# 01SignalDetect.net
KiCad netlist of a schematic drawn in Altium Designer
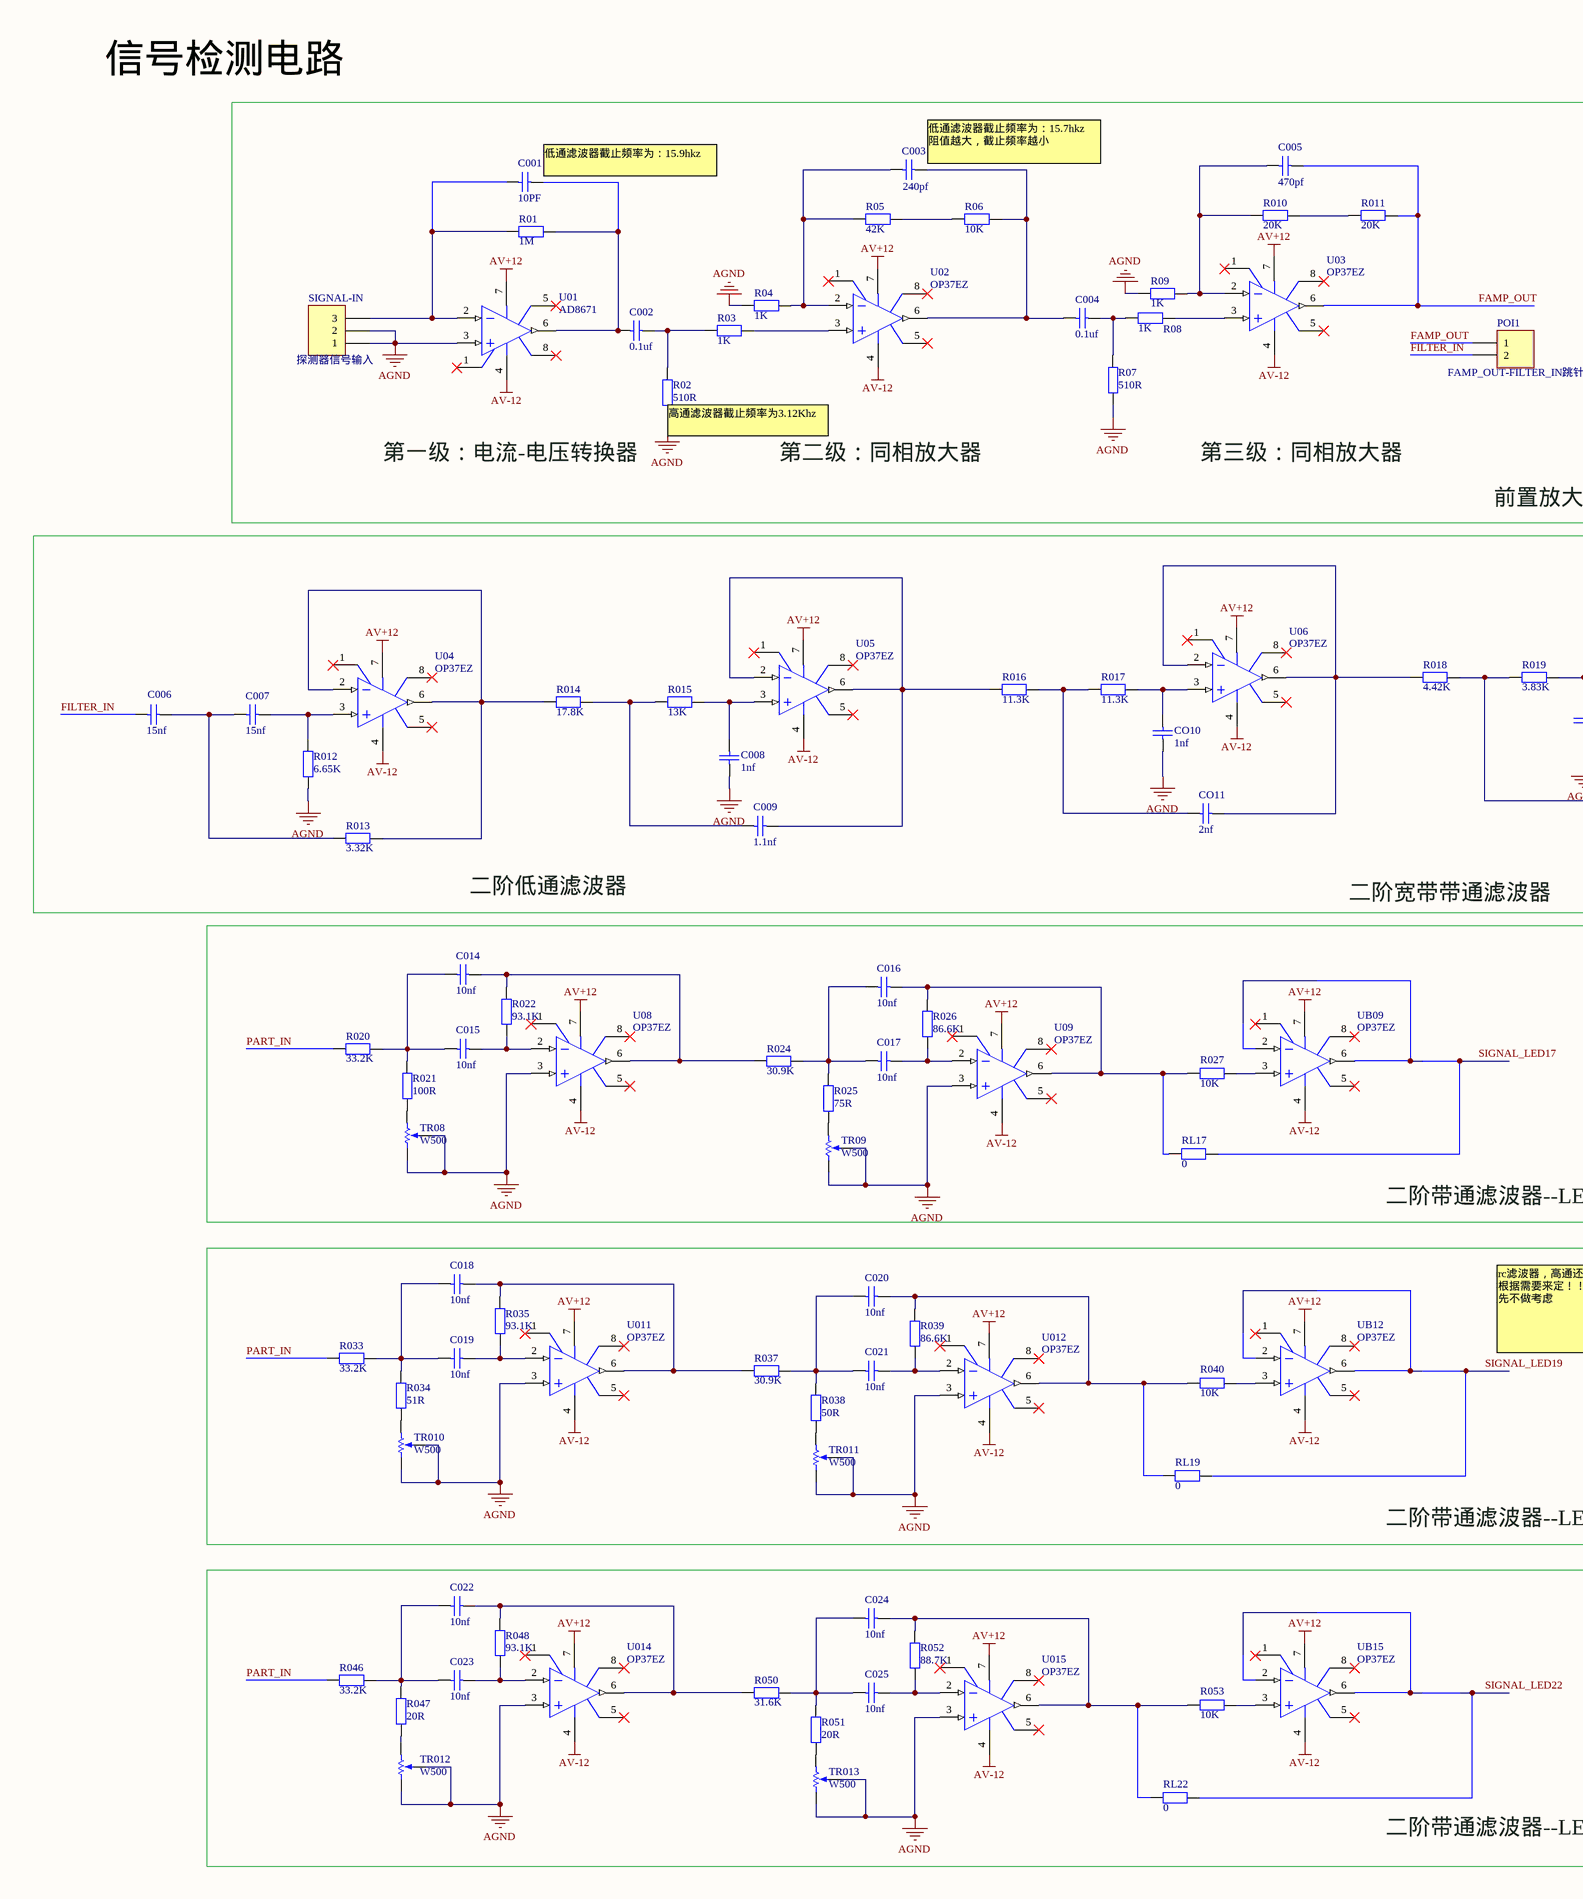
[diagram p0: 01SignalDetect.SchDoc, left]
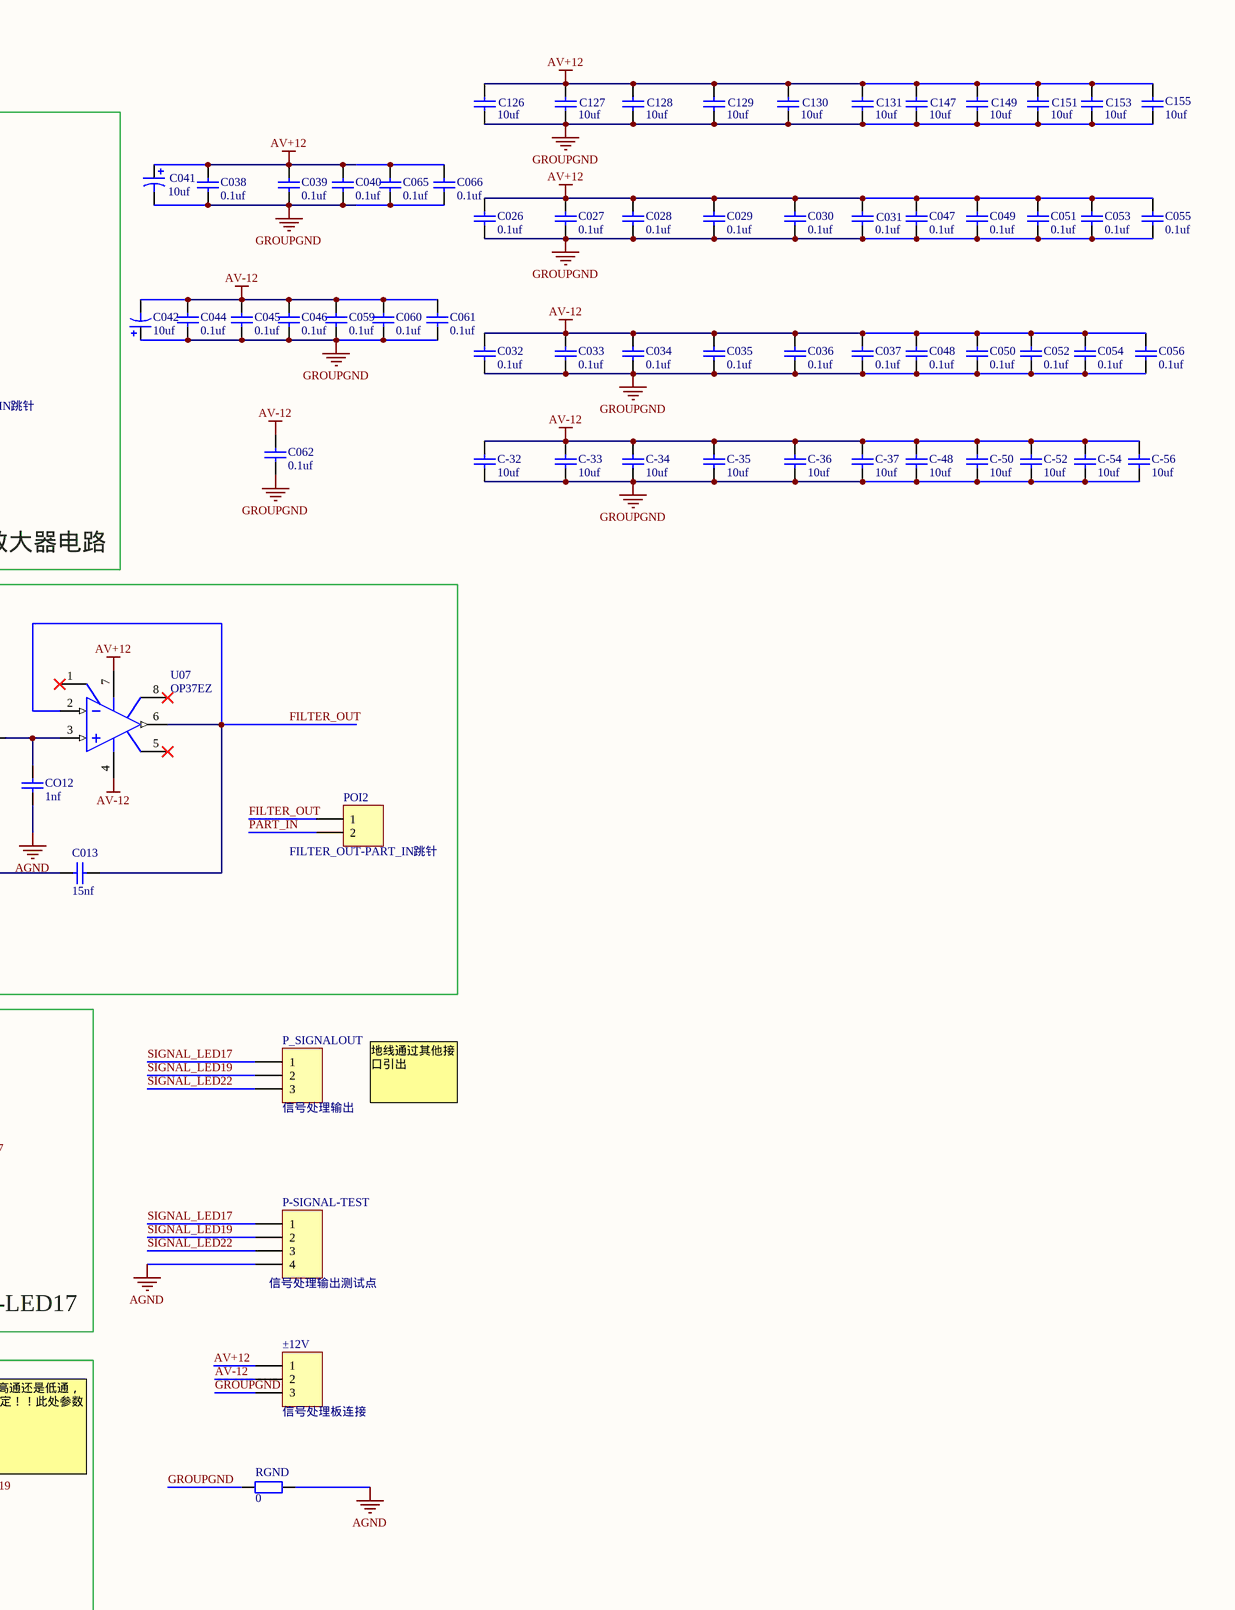
[diagram p1: 01SignalDetect.SchDoc, right]

(export (version "E")
  (design (tool "Eeschema 10.0.6"))
  (components
    (comp (ref "C-32")
      (value "10uf")
      (footprint "CC0805")
      (description "Capacitor")
      (fields (field (name "Comment") "Cap") (field (name "PUBLISHER") "Altium Limited"))
      (libsource (lib "Miscellaneous Devices") (part "Cap"))
    )
    (comp (ref "C-33")
      (value "10uf")
      (footprint "CC0805")
      (description "Capacitor")
      (fields (field (name "Comment") "Cap") (field (name "PUBLISHER") "Altium Limited"))
      (libsource (lib "Miscellaneous Devices") (part "Cap"))
    )
    (comp (ref "C-34")
      (value "10uf")
      (footprint "CC0805")
      (description "Capacitor")
      (fields (field (name "Comment") "Cap") (field (name "PUBLISHER") "Altium Limited"))
      (libsource (lib "Miscellaneous Devices") (part "Cap"))
    )
    (comp (ref "C-35")
      (value "10uf")
      (footprint "CC0805")
      (description "Capacitor")
      (fields (field (name "Comment") "Cap") (field (name "PUBLISHER") "Altium Limited"))
      (libsource (lib "Miscellaneous Devices") (part "Cap"))
    )
    (comp (ref "C-36")
      (value "10uf")
      (footprint "CC0805")
      (description "Capacitor")
      (fields (field (name "Comment") "Cap") (field (name "PUBLISHER") "Altium Limited"))
      (libsource (lib "Miscellaneous Devices") (part "Cap"))
    )
    (comp (ref "C-37")
      (value "10uf")
      (footprint "CC0805")
      (description "Capacitor")
      (fields (field (name "Comment") "Cap") (field (name "PUBLISHER") "Altium Limited"))
      (libsource (lib "Miscellaneous Devices") (part "Cap"))
    )
    (comp (ref "C-48")
      (value "10uf")
      (footprint "CC0805")
      (description "Capacitor")
      (fields (field (name "Comment") "Cap") (field (name "PUBLISHER") "Altium Limited"))
      (libsource (lib "Miscellaneous Devices") (part "Cap"))
    )
    (comp (ref "C-50")
      (value "10uf")
      (footprint "CC0805")
      (description "Capacitor")
      (fields (field (name "Comment") "Cap") (field (name "PUBLISHER") "Altium Limited"))
      (libsource (lib "Miscellaneous Devices") (part "Cap"))
    )
    (comp (ref "C-52")
      (value "10uf")
      (footprint "CC0805")
      (description "Capacitor")
      (fields (field (name "Comment") "Cap") (field (name "PUBLISHER") "Altium Limited"))
      (libsource (lib "Miscellaneous Devices") (part "Cap"))
    )
    (comp (ref "C-54")
      (value "10uf")
      (footprint "CC0805")
      (description "Capacitor")
      (fields (field (name "Comment") "Cap") (field (name "PUBLISHER") "Altium Limited"))
      (libsource (lib "Miscellaneous Devices") (part "Cap"))
    )
    (comp (ref "C-56")
      (value "10uf")
      (footprint "CC0805")
      (description "Capacitor")
      (fields (field (name "Comment") "Cap") (field (name "PUBLISHER") "Altium Limited"))
      (libsource (lib "Miscellaneous Devices") (part "Cap"))
    )
    (comp (ref "C001")
      (value "10PF")
      (footprint "CC0805")
      (description "Capacitor")
      (fields (field (name "Comment") "Cap") (field (name "PUBLISHER") "Altium Limited"))
      (libsource (lib "Miscellaneous Devices") (part "Cap"))
    )
    (comp (ref "C002")
      (value "0.1uf")
      (footprint "CC0805")
      (description "Capacitor")
      (fields (field (name "Comment") "Cap") (field (name "PUBLISHER") "Altium Limited"))
      (libsource (lib "Miscellaneous Devices") (part "Cap"))
    )
    (comp (ref "C003")
      (value "240pf")
      (footprint "CC0805")
      (description "Capacitor")
      (fields (field (name "Comment") "Cap") (field (name "PUBLISHER") "Altium Limited"))
      (libsource (lib "Miscellaneous Devices") (part "Cap"))
    )
    (comp (ref "C004")
      (value "0.1uf")
      (footprint "CC0805")
      (description "Capacitor")
      (fields (field (name "Comment") "Cap") (field (name "PUBLISHER") "Altium Limited"))
      (libsource (lib "Miscellaneous Devices") (part "Cap"))
    )
    (comp (ref "C005")
      (value "470pf")
      (footprint "CC0805")
      (description "Capacitor")
      (fields (field (name "Comment") "Cap") (field (name "PUBLISHER") "Altium Limited"))
      (libsource (lib "Miscellaneous Devices") (part "Cap"))
    )
    (comp (ref "C006")
      (value "15nf")
      (footprint "CC0805")
      (description "Capacitor")
      (fields (field (name "Comment") "Cap") (field (name "PUBLISHER") "Altium Limited"))
      (libsource (lib "Miscellaneous Devices") (part "Cap"))
    )
    (comp (ref "C007")
      (value "15nf")
      (footprint "CC0805")
      (description "Capacitor")
      (fields (field (name "Comment") "Cap") (field (name "PUBLISHER") "Altium Limited"))
      (libsource (lib "Miscellaneous Devices") (part "Cap"))
    )
    (comp (ref "C008")
      (value "1nf")
      (footprint "CC0805")
      (description "Capacitor")
      (fields (field (name "Comment") "Cap") (field (name "PUBLISHER") "Altium Limited"))
      (libsource (lib "Miscellaneous Devices") (part "Cap"))
    )
    (comp (ref "C009")
      (value "1.1nf")
      (footprint "CC0805")
      (description "Capacitor")
      (fields (field (name "Comment") "Cap") (field (name "PUBLISHER") "Altium Limited"))
      (libsource (lib "Miscellaneous Devices") (part "Cap"))
    )
    (comp (ref "C013")
      (value "15nf")
      (footprint "CC0805")
      (description "Capacitor")
      (fields (field (name "Comment") "Cap") (field (name "PUBLISHER") "Altium Limited"))
      (libsource (lib "Miscellaneous Devices") (part "Cap"))
    )
    (comp (ref "C014")
      (value "10nf")
      (footprint "校正电容")
      (description "Capacitor")
      (fields (field (name "Comment") "Cap") (field (name "PUBLISHER") "Altium Limited"))
      (libsource (lib "Miscellaneous Devices") (part "Cap"))
    )
    (comp (ref "C015")
      (value "10nf")
      (footprint "校正电容")
      (description "Capacitor")
      (fields (field (name "Comment") "Cap") (field (name "PUBLISHER") "Altium Limited"))
      (libsource (lib "Miscellaneous Devices") (part "Cap"))
    )
    (comp (ref "C016")
      (value "10nf")
      (footprint "校正电容")
      (description "Capacitor")
      (fields (field (name "Comment") "Cap") (field (name "PUBLISHER") "Altium Limited"))
      (libsource (lib "Miscellaneous Devices") (part "Cap"))
    )
    (comp (ref "C017")
      (value "10nf")
      (footprint "校正电容")
      (description "Capacitor")
      (fields (field (name "Comment") "Cap") (field (name "PUBLISHER") "Altium Limited"))
      (libsource (lib "Miscellaneous Devices") (part "Cap"))
    )
    (comp (ref "C018")
      (value "10nf")
      (footprint "校正电容")
      (description "Capacitor")
      (fields (field (name "Comment") "Cap") (field (name "PUBLISHER") "Altium Limited"))
      (libsource (lib "Miscellaneous Devices") (part "Cap"))
    )
    (comp (ref "C019")
      (value "10nf")
      (footprint "校正电容")
      (description "Capacitor")
      (fields (field (name "Comment") "Cap") (field (name "PUBLISHER") "Altium Limited"))
      (libsource (lib "Miscellaneous Devices") (part "Cap"))
    )
    (comp (ref "C020")
      (value "10nf")
      (footprint "校正电容")
      (description "Capacitor")
      (fields (field (name "Comment") "Cap") (field (name "PUBLISHER") "Altium Limited"))
      (libsource (lib "Miscellaneous Devices") (part "Cap"))
    )
    (comp (ref "C021")
      (value "10nf")
      (footprint "校正电容")
      (description "Capacitor")
      (fields (field (name "Comment") "Cap") (field (name "PUBLISHER") "Altium Limited"))
      (libsource (lib "Miscellaneous Devices") (part "Cap"))
    )
    (comp (ref "C022")
      (value "10nf")
      (footprint "校正电容")
      (description "Capacitor")
      (fields (field (name "Comment") "Cap") (field (name "PUBLISHER") "Altium Limited"))
      (libsource (lib "Miscellaneous Devices") (part "Cap"))
    )
    (comp (ref "C023")
      (value "10nf")
      (footprint "校正电容")
      (description "Capacitor")
      (fields (field (name "Comment") "Cap") (field (name "PUBLISHER") "Altium Limited"))
      (libsource (lib "Miscellaneous Devices") (part "Cap"))
    )
    (comp (ref "C024")
      (value "10nf")
      (footprint "校正电容")
      (description "Capacitor")
      (fields (field (name "Comment") "Cap") (field (name "PUBLISHER") "Altium Limited"))
      (libsource (lib "Miscellaneous Devices") (part "Cap"))
    )
    (comp (ref "C025")
      (value "10nf")
      (footprint "校正电容")
      (description "Capacitor")
      (fields (field (name "Comment") "Cap") (field (name "PUBLISHER") "Altium Limited"))
      (libsource (lib "Miscellaneous Devices") (part "Cap"))
    )
    (comp (ref "C026")
      (value "0.1uf")
      (footprint "CC0805")
      (description "Capacitor")
      (fields (field (name "Comment") "Cap") (field (name "PUBLISHER") "Altium Limited"))
      (libsource (lib "Miscellaneous Devices") (part "Cap"))
    )
    (comp (ref "C027")
      (value "0.1uf")
      (footprint "CC0805")
      (description "Capacitor")
      (fields (field (name "Comment") "Cap") (field (name "PUBLISHER") "Altium Limited"))
      (libsource (lib "Miscellaneous Devices") (part "Cap"))
    )
    (comp (ref "C028")
      (value "0.1uf")
      (footprint "CC0805")
      (description "Capacitor")
      (fields (field (name "Comment") "Cap") (field (name "PUBLISHER") "Altium Limited"))
      (libsource (lib "Miscellaneous Devices") (part "Cap"))
    )
    (comp (ref "C029")
      (value "0.1uf")
      (footprint "CC0805")
      (description "Capacitor")
      (fields (field (name "Comment") "Cap") (field (name "PUBLISHER") "Altium Limited"))
      (libsource (lib "Miscellaneous Devices") (part "Cap"))
    )
    (comp (ref "C030")
      (value "0.1uf")
      (footprint "CC0805")
      (description "Capacitor")
      (fields (field (name "Comment") "Cap") (field (name "PUBLISHER") "Altium Limited"))
      (libsource (lib "Miscellaneous Devices") (part "Cap"))
    )
    (comp (ref "C031")
      (value "0.1uf")
      (footprint "CC0805")
      (description "Capacitor")
      (fields (field (name "Comment") "Cap") (field (name "PUBLISHER") "Altium Limited"))
      (libsource (lib "Miscellaneous Devices") (part "Cap"))
    )
    (comp (ref "C032")
      (value "0.1uf")
      (footprint "CC0805")
      (description "Capacitor")
      (fields (field (name "Comment") "Cap") (field (name "PUBLISHER") "Altium Limited"))
      (libsource (lib "Miscellaneous Devices") (part "Cap"))
    )
    (comp (ref "C033")
      (value "0.1uf")
      (footprint "CC0805")
      (description "Capacitor")
      (fields (field (name "Comment") "Cap") (field (name "PUBLISHER") "Altium Limited"))
      (libsource (lib "Miscellaneous Devices") (part "Cap"))
    )
    (comp (ref "C034")
      (value "0.1uf")
      (footprint "CC0805")
      (description "Capacitor")
      (fields (field (name "Comment") "Cap") (field (name "PUBLISHER") "Altium Limited"))
      (libsource (lib "Miscellaneous Devices") (part "Cap"))
    )
    (comp (ref "C035")
      (value "0.1uf")
      (footprint "CC0805")
      (description "Capacitor")
      (fields (field (name "Comment") "Cap") (field (name "PUBLISHER") "Altium Limited"))
      (libsource (lib "Miscellaneous Devices") (part "Cap"))
    )
    (comp (ref "C036")
      (value "0.1uf")
      (footprint "CC0805")
      (description "Capacitor")
      (fields (field (name "Comment") "Cap") (field (name "PUBLISHER") "Altium Limited"))
      (libsource (lib "Miscellaneous Devices") (part "Cap"))
    )
    (comp (ref "C037")
      (value "0.1uf")
      (footprint "CC0805")
      (description "Capacitor")
      (fields (field (name "Comment") "Cap") (field (name "PUBLISHER") "Altium Limited"))
      (libsource (lib "Miscellaneous Devices") (part "Cap"))
    )
    (comp (ref "C038")
      (value "0.1uf")
      (footprint "CC0805")
      (description "Capacitor")
      (fields (field (name "Comment") "Cap") (field (name "PUBLISHER") "Altium Limited"))
      (libsource (lib "Miscellaneous Devices") (part "Cap"))
    )
    (comp (ref "C039")
      (value "0.1uf")
      (footprint "CC0805")
      (description "Capacitor")
      (fields (field (name "Comment") "Cap") (field (name "PUBLISHER") "Altium Limited"))
      (libsource (lib "Miscellaneous Devices") (part "Cap"))
    )
    (comp (ref "C040")
      (value "0.1uf")
      (footprint "CC0805")
      (description "Capacitor")
      (fields (field (name "Comment") "Cap") (field (name "PUBLISHER") "Altium Limited"))
      (libsource (lib "Miscellaneous Devices") (part "Cap"))
    )
    (comp (ref "C041")
      (value "10uf")
      (footprint "4*4.5 贴片电解电容")
      (description "Polarized Capacitor (Radial)")
      (fields (field (name "Comment") "Cap Pol1") (field (name "PUBLISHER") "Altium Limited"))
      (libsource (lib "Miscellaneous Devices") (part "Cap Pol1"))
    )
    (comp (ref "C042")
      (value "10uf")
      (footprint "4*4.5 贴片电解电容")
      (description "Polarized Capacitor (Radial)")
      (fields (field (name "Comment") "Cap Pol1") (field (name "PUBLISHER") "Altium Limited"))
      (libsource (lib "Miscellaneous Devices") (part "Cap Pol1"))
    )
    (comp (ref "C044")
      (value "0.1uf")
      (footprint "CC0805")
      (description "Capacitor")
      (fields (field (name "Comment") "Cap") (field (name "PUBLISHER") "Altium Limited"))
      (libsource (lib "Miscellaneous Devices") (part "Cap"))
    )
    (comp (ref "C045")
      (value "0.1uf")
      (footprint "CC0805")
      (description "Capacitor")
      (fields (field (name "Comment") "Cap") (field (name "PUBLISHER") "Altium Limited"))
      (libsource (lib "Miscellaneous Devices") (part "Cap"))
    )
    (comp (ref "C046")
      (value "0.1uf")
      (footprint "CC0805")
      (description "Capacitor")
      (fields (field (name "Comment") "Cap") (field (name "PUBLISHER") "Altium Limited"))
      (libsource (lib "Miscellaneous Devices") (part "Cap"))
    )
    (comp (ref "C047")
      (value "0.1uf")
      (footprint "CC0805")
      (description "Capacitor")
      (fields (field (name "Comment") "Cap") (field (name "PUBLISHER") "Altium Limited"))
      (libsource (lib "Miscellaneous Devices") (part "Cap"))
    )
    (comp (ref "C048")
      (value "0.1uf")
      (footprint "CC0805")
      (description "Capacitor")
      (fields (field (name "Comment") "Cap") (field (name "PUBLISHER") "Altium Limited"))
      (libsource (lib "Miscellaneous Devices") (part "Cap"))
    )
    (comp (ref "C049")
      (value "0.1uf")
      (footprint "CC0805")
      (description "Capacitor")
      (fields (field (name "Comment") "Cap") (field (name "PUBLISHER") "Altium Limited"))
      (libsource (lib "Miscellaneous Devices") (part "Cap"))
    )
    (comp (ref "C050")
      (value "0.1uf")
      (footprint "CC0805")
      (description "Capacitor")
      (fields (field (name "Comment") "Cap") (field (name "PUBLISHER") "Altium Limited"))
      (libsource (lib "Miscellaneous Devices") (part "Cap"))
    )
    (comp (ref "C051")
      (value "0.1uf")
      (footprint "CC0805")
      (description "Capacitor")
      (fields (field (name "Comment") "Cap") (field (name "PUBLISHER") "Altium Limited"))
      (libsource (lib "Miscellaneous Devices") (part "Cap"))
    )
    (comp (ref "C052")
      (value "0.1uf")
      (footprint "CC0805")
      (description "Capacitor")
      (fields (field (name "Comment") "Cap") (field (name "PUBLISHER") "Altium Limited"))
      (libsource (lib "Miscellaneous Devices") (part "Cap"))
    )
    (comp (ref "C053")
      (value "0.1uf")
      (footprint "CC0805")
      (description "Capacitor")
      (fields (field (name "Comment") "Cap") (field (name "PUBLISHER") "Altium Limited"))
      (libsource (lib "Miscellaneous Devices") (part "Cap"))
    )
    (comp (ref "C054")
      (value "0.1uf")
      (footprint "CC0805")
      (description "Capacitor")
      (fields (field (name "Comment") "Cap") (field (name "PUBLISHER") "Altium Limited"))
      (libsource (lib "Miscellaneous Devices") (part "Cap"))
    )
    (comp (ref "C055")
      (value "0.1uf")
      (footprint "CC0805")
      (description "Capacitor")
      (fields (field (name "Comment") "Cap") (field (name "PUBLISHER") "Altium Limited"))
      (libsource (lib "Miscellaneous Devices") (part "Cap"))
    )
    (comp (ref "C056")
      (value "0.1uf")
      (footprint "CC0805")
      (description "Capacitor")
      (fields (field (name "Comment") "Cap") (field (name "PUBLISHER") "Altium Limited"))
      (libsource (lib "Miscellaneous Devices") (part "Cap"))
    )
    (comp (ref "C059")
      (value "0.1uf")
      (footprint "CC0805")
      (description "Capacitor")
      (fields (field (name "Comment") "Cap") (field (name "PUBLISHER") "Altium Limited"))
      (libsource (lib "Miscellaneous Devices") (part "Cap"))
    )
    (comp (ref "C060")
      (value "0.1uf")
      (footprint "CC0805")
      (description "Capacitor")
      (fields (field (name "Comment") "Cap") (field (name "PUBLISHER") "Altium Limited"))
      (libsource (lib "Miscellaneous Devices") (part "Cap"))
    )
    (comp (ref "C061")
      (value "0.1uf")
      (footprint "CC0805")
      (description "Capacitor")
      (fields (field (name "Comment") "Cap") (field (name "PUBLISHER") "Altium Limited"))
      (libsource (lib "Miscellaneous Devices") (part "Cap"))
    )
    (comp (ref "C062")
      (value "0.1uf")
      (footprint "CC0805")
      (description "Capacitor")
      (fields (field (name "Comment") "Cap") (field (name "PUBLISHER") "Altium Limited"))
      (libsource (lib "Miscellaneous Devices") (part "Cap"))
    )
    (comp (ref "C065")
      (value "0.1uf")
      (footprint "CC0805")
      (description "Capacitor")
      (fields (field (name "Comment") "Cap") (field (name "PUBLISHER") "Altium Limited"))
      (libsource (lib "Miscellaneous Devices") (part "Cap"))
    )
    (comp (ref "C066")
      (value "0.1uf")
      (footprint "CC0805")
      (description "Capacitor")
      (fields (field (name "Comment") "Cap") (field (name "PUBLISHER") "Altium Limited"))
      (libsource (lib "Miscellaneous Devices") (part "Cap"))
    )
    (comp (ref "C126")
      (value "10uf")
      (footprint "CC0805")
      (description "Capacitor")
      (fields (field (name "Comment") "Cap") (field (name "PUBLISHER") "Altium Limited"))
      (libsource (lib "Miscellaneous Devices") (part "Cap"))
    )
    (comp (ref "C127")
      (value "10uf")
      (footprint "CC0805")
      (description "Capacitor")
      (fields (field (name "Comment") "Cap") (field (name "PUBLISHER") "Altium Limited"))
      (libsource (lib "Miscellaneous Devices") (part "Cap"))
    )
    (comp (ref "C128")
      (value "10uf")
      (footprint "CC0805")
      (description "Capacitor")
      (fields (field (name "Comment") "Cap") (field (name "PUBLISHER") "Altium Limited"))
      (libsource (lib "Miscellaneous Devices") (part "Cap"))
    )
    (comp (ref "C129")
      (value "10uf")
      (footprint "CC0805")
      (description "Capacitor")
      (fields (field (name "Comment") "Cap") (field (name "PUBLISHER") "Altium Limited"))
      (libsource (lib "Miscellaneous Devices") (part "Cap"))
    )
    (comp (ref "C130")
      (value "10uf")
      (footprint "CC0805")
      (description "Capacitor")
      (fields (field (name "Comment") "Cap") (field (name "PUBLISHER") "Altium Limited"))
      (libsource (lib "Miscellaneous Devices") (part "Cap"))
    )
    (comp (ref "C131")
      (value "10uf")
      (footprint "CC0805")
      (description "Capacitor")
      (fields (field (name "Comment") "Cap") (field (name "PUBLISHER") "Altium Limited"))
      (libsource (lib "Miscellaneous Devices") (part "Cap"))
    )
    (comp (ref "C147")
      (value "10uf")
      (footprint "CC0805")
      (description "Capacitor")
      (fields (field (name "Comment") "Cap") (field (name "PUBLISHER") "Altium Limited"))
      (libsource (lib "Miscellaneous Devices") (part "Cap"))
    )
    (comp (ref "C149")
      (value "10uf")
      (footprint "CC0805")
      (description "Capacitor")
      (fields (field (name "Comment") "Cap") (field (name "PUBLISHER") "Altium Limited"))
      (libsource (lib "Miscellaneous Devices") (part "Cap"))
    )
    (comp (ref "C151")
      (value "10uf")
      (footprint "CC0805")
      (description "Capacitor")
      (fields (field (name "Comment") "Cap") (field (name "PUBLISHER") "Altium Limited"))
      (libsource (lib "Miscellaneous Devices") (part "Cap"))
    )
    (comp (ref "C153")
      (value "10uf")
      (footprint "CC0805")
      (description "Capacitor")
      (fields (field (name "Comment") "Cap") (field (name "PUBLISHER") "Altium Limited"))
      (libsource (lib "Miscellaneous Devices") (part "Cap"))
    )
    (comp (ref "C155")
      (value "10uf")
      (footprint "CC0805")
      (description "Capacitor")
      (fields (field (name "Comment") "Cap") (field (name "PUBLISHER") "Altium Limited"))
      (libsource (lib "Miscellaneous Devices") (part "Cap"))
    )
    (comp (ref "CO10")
      (value "1nf")
      (footprint "CC0805")
      (description "Capacitor")
      (fields (field (name "Comment") "Cap") (field (name "PUBLISHER") "Altium Limited"))
      (libsource (lib "Miscellaneous Devices") (part "Cap"))
    )
    (comp (ref "CO11")
      (value "2nf")
      (footprint "CC0805")
      (description "Capacitor")
      (fields (field (name "Comment") "Cap") (field (name "PUBLISHER") "Altium Limited"))
      (libsource (lib "Miscellaneous Devices") (part "Cap"))
    )
    (comp (ref "CO12")
      (value "1nf")
      (footprint "CC0805")
      (description "Capacitor")
      (fields (field (name "Comment") "Cap") (field (name "PUBLISHER") "Altium Limited"))
      (libsource (lib "Miscellaneous Devices") (part "Cap"))
    )
    (comp (ref "P-SIGNAL-TEST")
      (value "信号处理输出测试点")
      (footprint "HDR1X4")
      (description "Header, 4-Pin")
      (fields (field (name "PUBLISHER") "Altium Limited"))
      (libsource (lib "Miscellaneous Connectors") (part "Header 4"))
    )
    (comp (ref "POI1")
      (value "FAMP_OUT-FILTER_IN跳针")
      (footprint "HDR1X2")
      (description "Header, 2-Pin")
      (fields (field (name "PUBLISHER") "Altium Limited"))
      (libsource (lib "Miscellaneous Connectors") (part "Header 2"))
    )
    (comp (ref "POI2")
      (value "FILTER_OUT-PART_IN跳针")
      (footprint "HDR1X2")
      (description "Header, 2-Pin")
      (fields (field (name "PUBLISHER") "Altium Limited"))
      (libsource (lib "Miscellaneous Connectors") (part "Header 2"))
    )
    (comp (ref "P_SIGNALOUT")
      (value "信号处理输出")
      (footprint "HDR1X3H")
      (description "Header, 3-Pin, Right Angle")
      (fields (field (name "PUBLISHER") "Altium Limited"))
      (libsource (lib "Miscellaneous Connectors") (part "Header 3H"))
    )
    (comp (ref "R01")
      (value "1M")
      (footprint "AXIAL-0.4")
      (description "Resistor")
      (fields (field (name "Comment") "Res2") (field (name "PUBLISHER") "Altium Limited"))
      (libsource (lib "") (part "Res2_1"))
    )
    (comp (ref "R02")
      (value "510R")
      (footprint "0805")
      (description "Resistor")
      (fields (field (name "Comment") "Res2") (field (name "PUBLISHER") "Altium Limited"))
      (libsource (lib "Miscellaneous Devices") (part "Res2"))
    )
    (comp (ref "R03")
      (value "1K")
      (footprint "0805")
      (description "Resistor")
      (fields (field (name "Comment") "Res2") (field (name "PUBLISHER") "Altium Limited"))
      (libsource (lib "") (part "Res2_1"))
    )
    (comp (ref "R04")
      (value "1K")
      (footprint "0805")
      (description "Resistor")
      (fields (field (name "Comment") "Res2") (field (name "PUBLISHER") "Altium Limited"))
      (libsource (lib "") (part "Res2_1"))
    )
    (comp (ref "R05")
      (value "42K")
      (footprint "0805")
      (description "Resistor")
      (fields (field (name "Comment") "Res2") (field (name "PUBLISHER") "Altium Limited"))
      (libsource (lib "") (part "Res2_1"))
    )
    (comp (ref "R06")
      (value "10K")
      (footprint "张宝俊封装库:0805")
      (description "Resistor")
      (fields (field (name "Comment") "Res2") (field (name "PUBLISHER") "Altium Limited"))
      (libsource (lib "") (part "Res2_1"))
    )
    (comp (ref "R07")
      (value "510R")
      (footprint "0805")
      (description "Resistor")
      (fields (field (name "Comment") "Res2") (field (name "PUBLISHER") "Altium Limited"))
      (libsource (lib "Miscellaneous Devices") (part "Res2"))
    )
    (comp (ref "R08")
      (value "1K")
      (footprint "0805")
      (description "Resistor")
      (fields (field (name "Comment") "Res2") (field (name "PUBLISHER") "Altium Limited"))
      (libsource (lib "") (part "Res2_1"))
    )
    (comp (ref "R09")
      (value "1K")
      (footprint "0805")
      (description "Resistor")
      (fields (field (name "Comment") "Res2") (field (name "PUBLISHER") "Altium Limited"))
      (libsource (lib "") (part "Res2_1"))
    )
    (comp (ref "R010")
      (value "20K")
      (footprint "0805")
      (description "Resistor")
      (fields (field (name "Comment") "Res2") (field (name "PUBLISHER") "Altium Limited"))
      (libsource (lib "") (part "Res2_1"))
    )
    (comp (ref "R011")
      (value "20K")
      (footprint "张宝俊封装库:0805")
      (description "Resistor")
      (fields (field (name "Comment") "Res2") (field (name "PUBLISHER") "Altium Limited"))
      (libsource (lib "") (part "Res2_1"))
    )
    (comp (ref "R012")
      (value "6.65K")
      (footprint "0805")
      (description "Resistor")
      (fields (field (name "Comment") "Res2") (field (name "PUBLISHER") "Altium Limited"))
      (libsource (lib "Miscellaneous Devices") (part "Res2"))
    )
    (comp (ref "R013")
      (value "3.32K")
      (footprint "0805")
      (description "Resistor")
      (fields (field (name "Comment") "Res2") (field (name "PUBLISHER") "Altium Limited"))
      (libsource (lib "") (part "Res2_2"))
    )
    (comp (ref "R014")
      (value "17.8K")
      (footprint "0805")
      (description "Resistor")
      (fields (field (name "Comment") "Res2") (field (name "PUBLISHER") "Altium Limited"))
      (libsource (lib "") (part "Res2_1"))
    )
    (comp (ref "R015")
      (value "13K")
      (footprint "0805")
      (description "Resistor")
      (fields (field (name "Comment") "Res2") (field (name "PUBLISHER") "Altium Limited"))
      (libsource (lib "") (part "Res2_2"))
    )
    (comp (ref "R016")
      (value "11.3K")
      (footprint "0805")
      (description "Resistor")
      (fields (field (name "Comment") "Res2") (field (name "PUBLISHER") "Altium Limited"))
      (libsource (lib "") (part "Res2_1"))
    )
    (comp (ref "R017")
      (value "11.3K")
      (footprint "0805")
      (description "Resistor")
      (fields (field (name "Comment") "Res2") (field (name "PUBLISHER") "Altium Limited"))
      (libsource (lib "") (part "Res2_1"))
    )
    (comp (ref "R018")
      (value "4.42K")
      (footprint "0805")
      (description "Resistor")
      (fields (field (name "Comment") "Res2") (field (name "PUBLISHER") "Altium Limited"))
      (libsource (lib "") (part "Res2_1"))
    )
    (comp (ref "R019")
      (value "3.83K")
      (footprint "0805")
      (description "Resistor")
      (fields (field (name "Comment") "Res2") (field (name "PUBLISHER") "Altium Limited"))
      (libsource (lib "") (part "Res2_1"))
    )
    (comp (ref "R020")
      (value "33.2K")
      (footprint "0805")
      (description "Resistor")
      (fields (field (name "Comment") "Res2") (field (name "PUBLISHER") "Altium Limited"))
      (libsource (lib "") (part "Res2_1"))
    )
    (comp (ref "R021")
      (value "100R")
      (footprint "0805")
      (description "Resistor")
      (fields (field (name "Comment") "Res2") (field (name "PUBLISHER") "Altium Limited"))
      (libsource (lib "Miscellaneous Devices") (part "Res2"))
    )
    (comp (ref "R022")
      (value "93.1K")
      (footprint "0805")
      (description "Resistor")
      (fields (field (name "Comment") "Res2") (field (name "PUBLISHER") "Altium Limited"))
      (libsource (lib "Miscellaneous Devices") (part "Res2"))
    )
    (comp (ref "R024")
      (value "30.9K")
      (footprint "0805")
      (description "Resistor")
      (fields (field (name "Comment") "Res2") (field (name "PUBLISHER") "Altium Limited"))
      (libsource (lib "") (part "Res2_1"))
    )
    (comp (ref "R025")
      (value "75R")
      (footprint "0805")
      (description "Resistor")
      (fields (field (name "Comment") "Res2") (field (name "PUBLISHER") "Altium Limited"))
      (libsource (lib "Miscellaneous Devices") (part "Res2"))
    )
    (comp (ref "R026")
      (value "86.6K")
      (footprint "0805")
      (description "Resistor")
      (fields (field (name "Comment") "Res2") (field (name "PUBLISHER") "Altium Limited"))
      (libsource (lib "Miscellaneous Devices") (part "Res2"))
    )
    (comp (ref "R027")
      (value "10K")
      (footprint "0805")
      (description "Resistor")
      (fields (field (name "Comment") "Res2") (field (name "PUBLISHER") "Altium Limited"))
      (libsource (lib "") (part "Res2_2"))
    )
    (comp (ref "R033")
      (value "33.2K")
      (footprint "0805")
      (description "Resistor")
      (fields (field (name "Comment") "Res2") (field (name "PUBLISHER") "Altium Limited"))
      (libsource (lib "") (part "Res2_1"))
    )
    (comp (ref "R034")
      (value "51R")
      (footprint "0805")
      (description "Resistor")
      (fields (field (name "Comment") "Res2") (field (name "PUBLISHER") "Altium Limited"))
      (libsource (lib "Miscellaneous Devices") (part "Res2"))
    )
    (comp (ref "R035")
      (value "93.1K")
      (footprint "0805")
      (description "Resistor")
      (fields (field (name "Comment") "Res2") (field (name "PUBLISHER") "Altium Limited"))
      (libsource (lib "Miscellaneous Devices") (part "Res2"))
    )
    (comp (ref "R037")
      (value "30.9K")
      (footprint "0805")
      (description "Resistor")
      (fields (field (name "Comment") "Res2") (field (name "PUBLISHER") "Altium Limited"))
      (libsource (lib "") (part "Res2_1"))
    )
    (comp (ref "R038")
      (value "50R")
      (footprint "0805")
      (description "Resistor")
      (fields (field (name "Comment") "Res2") (field (name "PUBLISHER") "Altium Limited"))
      (libsource (lib "Miscellaneous Devices") (part "Res2"))
    )
    (comp (ref "R039")
      (value "86.6K")
      (footprint "0805")
      (description "Resistor")
      (fields (field (name "Comment") "Res2") (field (name "PUBLISHER") "Altium Limited"))
      (libsource (lib "Miscellaneous Devices") (part "Res2"))
    )
    (comp (ref "R040")
      (value "10K")
      (footprint "0805")
      (description "Resistor")
      (fields (field (name "Comment") "Res2") (field (name "PUBLISHER") "Altium Limited"))
      (libsource (lib "") (part "Res2_2"))
    )
    (comp (ref "R046")
      (value "33.2K")
      (footprint "0805")
      (description "Resistor")
      (fields (field (name "Comment") "Res2") (field (name "PUBLISHER") "Altium Limited"))
      (libsource (lib "") (part "Res2_1"))
    )
    (comp (ref "R047")
      (value "20R")
      (footprint "0805")
      (description "Resistor")
      (fields (field (name "Comment") "Res2") (field (name "PUBLISHER") "Altium Limited"))
      (libsource (lib "Miscellaneous Devices") (part "Res2"))
    )
    (comp (ref "R048")
      (value "93.1K")
      (footprint "0805")
      (description "Resistor")
      (fields (field (name "Comment") "Res2") (field (name "PUBLISHER") "Altium Limited"))
      (libsource (lib "Miscellaneous Devices") (part "Res2"))
    )
    (comp (ref "R050")
      (value "31.6K")
      (footprint "0805")
      (description "Resistor")
      (fields (field (name "Comment") "Res2") (field (name "PUBLISHER") "Altium Limited"))
      (libsource (lib "") (part "Res2_1"))
    )
    (comp (ref "R051")
      (value "20R")
      (footprint "0805")
      (description "Resistor")
      (fields (field (name "Comment") "Res2") (field (name "PUBLISHER") "Altium Limited"))
      (libsource (lib "Miscellaneous Devices") (part "Res2"))
    )
    (comp (ref "R052")
      (value "88.7K")
      (footprint "0805")
      (description "Resistor")
      (fields (field (name "Comment") "Res2") (field (name "PUBLISHER") "Altium Limited"))
      (libsource (lib "Miscellaneous Devices") (part "Res2"))
    )
    (comp (ref "R053")
      (value "10K")
      (footprint "0805")
      (description "Resistor")
      (fields (field (name "Comment") "Res2") (field (name "PUBLISHER") "Altium Limited"))
      (libsource (lib "") (part "Res2_2"))
    )
    (comp (ref "RGND")
      (value "0")
      (footprint "0805")
      (description "Resistor")
      (fields (field (name "Comment") "Res2") (field (name "PUBLISHER") "Altium Limited"))
      (libsource (lib "") (part "Res2_2"))
    )
    (comp (ref "RL17")
      (value "0")
      (footprint "张宝俊封装库:0805")
      (description "Resistor")
      (fields (field (name "Comment") "Res2") (field (name "PUBLISHER") "Altium Limited"))
      (libsource (lib "") (part "Res2_2"))
    )
    (comp (ref "RL19")
      (value "0")
      (footprint "张宝俊封装库:0805")
      (description "Resistor")
      (fields (field (name "Comment") "Res2") (field (name "PUBLISHER") "Altium Limited"))
      (libsource (lib "") (part "Res2_2"))
    )
    (comp (ref "RL22")
      (value "0")
      (footprint "张宝俊封装库:0805")
      (description "Resistor")
      (fields (field (name "Comment") "Res2") (field (name "PUBLISHER") "Altium Limited"))
      (libsource (lib "") (part "Res2_2"))
    )
    (comp (ref "SIGNAL-IN")
      (value "探测器信号输入")
      (footprint "HDR1X3H")
      (description "Header, 3-Pin, Right Angle")
      (fields (field (name "PUBLISHER") "Altium Limited"))
      (libsource (lib "") (part "Header 3H_1"))
    )
    (comp (ref "TR08")
      (value "W500")
      (footprint "VR5")
      (description "Potentiometer")
      (fields (field (name "Comment") "RPot") (field (name "PUBLISHER") "Altium Limited"))
      (libsource (lib "Miscellaneous Devices") (part "RPot"))
    )
    (comp (ref "TR09")
      (value "W500")
      (footprint "VR5")
      (description "Potentiometer")
      (fields (field (name "Comment") "RPot") (field (name "PUBLISHER") "Altium Limited"))
      (libsource (lib "Miscellaneous Devices") (part "RPot"))
    )
    (comp (ref "TR010")
      (value "W500")
      (footprint "VR5")
      (description "Potentiometer")
      (fields (field (name "Comment") "RPot") (field (name "PUBLISHER") "Altium Limited"))
      (libsource (lib "Miscellaneous Devices") (part "RPot"))
    )
    (comp (ref "TR011")
      (value "W500")
      (footprint "VR5")
      (description "Potentiometer")
      (fields (field (name "Comment") "RPot") (field (name "PUBLISHER") "Altium Limited"))
      (libsource (lib "Miscellaneous Devices") (part "RPot"))
    )
    (comp (ref "TR012")
      (value "W500")
      (footprint "VR5")
      (description "Potentiometer")
      (fields (field (name "Comment") "RPot") (field (name "PUBLISHER") "Altium Limited"))
      (libsource (lib "Miscellaneous Devices") (part "RPot"))
    )
    (comp (ref "TR013")
      (value "W500")
      (footprint "VR5")
      (description "Potentiometer")
      (fields (field (name "Comment") "RPot") (field (name "PUBLISHER") "Altium Limited"))
      (libsource (lib "Miscellaneous Devices") (part "RPot"))
    )
    (comp (ref "U01")
      (value "AD8671")
      (footprint "SO-8-N")
      (description "Low-Noise, Precision Operational Amplifier")
      (fields (field (name "PUBLISHER") "Altium Limited"))
      (libsource (lib "AD Operational Amplifier") (part "OP27FJ"))
    )
    (comp (ref "U02")
      (value "OP37EZ")
      (footprint "SO-8-N")
      (description "Low-Noise, Precision, High-Speed Operational Amplifier (Avcl >= 5)")
      (fields (field (name "PUBLISHER") "Altium Limited"))
      (libsource (lib "AD Operational Amplifier") (part "OP37EZ"))
    )
    (comp (ref "U03")
      (value "OP37EZ")
      (footprint "SO-8-N")
      (description "Low-Noise, Precision, High-Speed Operational Amplifier (Avcl >= 5)")
      (fields (field (name "PUBLISHER") "Altium Limited"))
      (libsource (lib "AD Operational Amplifier") (part "OP37EZ"))
    )
    (comp (ref "U04")
      (value "OP37EZ")
      (footprint "SO-8-N")
      (description "Low-Noise, Precision, High-Speed Operational Amplifier (Avcl >= 5)")
      (fields (field (name "PUBLISHER") "Altium Limited"))
      (libsource (lib "AD Operational Amplifier") (part "OP37EZ"))
    )
    (comp (ref "U05")
      (value "OP37EZ")
      (footprint "SO-8-N")
      (description "Low-Noise, Precision, High-Speed Operational Amplifier (Avcl >= 5)")
      (fields (field (name "PUBLISHER") "Altium Limited"))
      (libsource (lib "AD Operational Amplifier") (part "OP37EZ"))
    )
    (comp (ref "U06")
      (value "OP37EZ")
      (footprint "SO-8-N")
      (description "Low-Noise, Precision, High-Speed Operational Amplifier (Avcl >= 5)")
      (fields (field (name "PUBLISHER") "Altium Limited"))
      (libsource (lib "AD Operational Amplifier") (part "OP37EZ"))
    )
    (comp (ref "U07")
      (value "OP37EZ")
      (footprint "SO-8-N")
      (description "Low-Noise, Precision, High-Speed Operational Amplifier (Avcl >= 5)")
      (fields (field (name "PUBLISHER") "Altium Limited"))
      (libsource (lib "AD Operational Amplifier") (part "OP37EZ"))
    )
    (comp (ref "U08")
      (value "OP37EZ")
      (footprint "SO-8-N")
      (description "Low-Noise, Precision, High-Speed Operational Amplifier (Avcl >= 5)")
      (fields (field (name "PUBLISHER") "Altium Limited"))
      (libsource (lib "AD Operational Amplifier") (part "OP37EZ"))
    )
    (comp (ref "U09")
      (value "OP37EZ")
      (footprint "SO-8-N")
      (description "Low-Noise, Precision, High-Speed Operational Amplifier (Avcl >= 5)")
      (fields (field (name "PUBLISHER") "Altium Limited"))
      (libsource (lib "AD Operational Amplifier") (part "OP37EZ"))
    )
    (comp (ref "U011")
      (value "OP37EZ")
      (footprint "SO-8-N")
      (description "Low-Noise, Precision, High-Speed Operational Amplifier (Avcl >= 5)")
      (fields (field (name "PUBLISHER") "Altium Limited"))
      (libsource (lib "AD Operational Amplifier") (part "OP37EZ"))
    )
    (comp (ref "U012")
      (value "OP37EZ")
      (footprint "SO-8-N")
      (description "Low-Noise, Precision, High-Speed Operational Amplifier (Avcl >= 5)")
      (fields (field (name "PUBLISHER") "Altium Limited"))
      (libsource (lib "AD Operational Amplifier") (part "OP37EZ"))
    )
    (comp (ref "U014")
      (value "OP37EZ")
      (footprint "SO-8-N")
      (description "Low-Noise, Precision, High-Speed Operational Amplifier (Avcl >= 5)")
      (fields (field (name "PUBLISHER") "Altium Limited"))
      (libsource (lib "AD Operational Amplifier") (part "OP37EZ"))
    )
    (comp (ref "U015")
      (value "OP37EZ")
      (footprint "SO-8-N")
      (description "Low-Noise, Precision, High-Speed Operational Amplifier (Avcl >= 5)")
      (fields (field (name "PUBLISHER") "Altium Limited"))
      (libsource (lib "AD Operational Amplifier") (part "OP37EZ"))
    )
    (comp (ref "UB09")
      (value "OP37EZ")
      (footprint "SO-8-N")
      (description "Low-Noise, Precision, High-Speed Operational Amplifier (Avcl >= 5)")
      (fields (field (name "PUBLISHER") "Altium Limited"))
      (libsource (lib "AD Operational Amplifier") (part "OP37EZ"))
    )
    (comp (ref "UB12")
      (value "OP37EZ")
      (footprint "SO-8-N")
      (description "Low-Noise, Precision, High-Speed Operational Amplifier (Avcl >= 5)")
      (fields (field (name "PUBLISHER") "Altium Limited"))
      (libsource (lib "AD Operational Amplifier") (part "OP37EZ"))
    )
    (comp (ref "UB15")
      (value "OP37EZ")
      (footprint "SO-8-N")
      (description "Low-Noise, Precision, High-Speed Operational Amplifier (Avcl >= 5)")
      (fields (field (name "PUBLISHER") "Altium Limited"))
      (libsource (lib "AD Operational Amplifier") (part "OP37EZ"))
    )
    (comp (ref "±12V")
      (value "信号处理板连接")
      (footprint "HDR1X3H")
      (description "Header, 3-Pin, Right Angle")
      (fields (field (name "PUBLISHER") "Altium Limited"))
      (libsource (lib "Miscellaneous Connectors") (part "Header 3H"))
    )
  )
  (nets
    (net (code "1") (name "/FAMP_OUT") (class "Default")
      (node (ref "C005") (pin "1") (pinfunction "1_1") (pintype "passive"))
      (node (ref "POI1") (pin "1") (pinfunction "1_1") (pintype "passive"))
      (node (ref "R011") (pin "2") (pinfunction "2_2") (pintype "passive"))
      (node (ref "U03") (pin "6") (pinfunction "OUT_6") (pintype "output"))
    )
    (net (code "2") (name "/FILTER_IN") (class "Default")
      (node (ref "C006") (pin "2") (pinfunction "2_2") (pintype "passive"))
      (node (ref "POI1") (pin "2") (pinfunction "2_2") (pintype "passive"))
    )
    (net (code "3") (name "/FILTER_OUT") (class "Default")
      (node (ref "C013") (pin "1") (pinfunction "1_1") (pintype "passive"))
      (node (ref "POI2") (pin "1") (pinfunction "1_1") (pintype "passive"))
      (node (ref "U07") (pin "2") (pinfunction "IN-_2") (pintype "input"))
      (node (ref "U07") (pin "6") (pinfunction "OUT_6") (pintype "output"))
    )
    (net (code "4") (name "/PART_IN") (class "Default")
      (node (ref "POI2") (pin "2") (pinfunction "2_2") (pintype "passive"))
      (node (ref "R020") (pin "1") (pinfunction "1_1") (pintype "passive"))
      (node (ref "R033") (pin "1") (pinfunction "1_1") (pintype "passive"))
      (node (ref "R046") (pin "1") (pinfunction "1_1") (pintype "passive"))
    )
    (net (code "5") (name "/SIGNAL_LED17") (class "Default")
      (node (ref "P-SIGNAL-TEST") (pin "1") (pinfunction "1_1") (pintype "passive"))
      (node (ref "P_SIGNALOUT") (pin "1") (pinfunction "1_1") (pintype "passive"))
      (node (ref "RL17") (pin "1") (pinfunction "1_1") (pintype "passive"))
      (node (ref "UB09") (pin "2") (pinfunction "IN-_2") (pintype "input"))
      (node (ref "UB09") (pin "6") (pinfunction "OUT_6") (pintype "output"))
    )
    (net (code "6") (name "/SIGNAL_LED19") (class "Default")
      (node (ref "P-SIGNAL-TEST") (pin "2") (pinfunction "2_2") (pintype "passive"))
      (node (ref "P_SIGNALOUT") (pin "2") (pinfunction "2_2") (pintype "passive"))
      (node (ref "RL19") (pin "1") (pinfunction "1_1") (pintype "passive"))
      (node (ref "UB12") (pin "2") (pinfunction "IN-_2") (pintype "input"))
      (node (ref "UB12") (pin "6") (pinfunction "OUT_6") (pintype "output"))
    )
    (net (code "7") (name "/SIGNAL_LED22") (class "Default")
      (node (ref "P-SIGNAL-TEST") (pin "3") (pinfunction "3_3") (pintype "passive"))
      (node (ref "P_SIGNALOUT") (pin "3") (pinfunction "3_3") (pintype "passive"))
      (node (ref "RL22") (pin "1") (pinfunction "1_1") (pintype "passive"))
      (node (ref "UB15") (pin "2") (pinfunction "IN-_2") (pintype "input"))
      (node (ref "UB15") (pin "6") (pinfunction "OUT_6") (pintype "output"))
    )
    (net (code "8") (name "AGND") (class "Default")
      (node (ref "C008") (pin "2") (pinfunction "2_2") (pintype "passive"))
      (node (ref "CO10") (pin "1") (pinfunction "1_1") (pintype "passive"))
      (node (ref "CO12") (pin "1") (pinfunction "1_1") (pintype "passive"))
      (node (ref "P-SIGNAL-TEST") (pin "4") (pinfunction "4_4") (pintype "passive"))
      (node (ref "R012") (pin "1") (pinfunction "1_1") (pintype "passive"))
      (node (ref "R02") (pin "1") (pinfunction "1_1") (pintype "passive"))
      (node (ref "R04") (pin "1") (pinfunction "1_1") (pintype "passive"))
      (node (ref "R07") (pin "1") (pinfunction "1_1") (pintype "passive"))
      (node (ref "R09") (pin "1") (pinfunction "1_1") (pintype "passive"))
      (node (ref "RGND") (pin "1") (pinfunction "1_1") (pintype "passive"))
      (node (ref "SIGNAL-IN") (pin "1") (pinfunction "1_1") (pintype "passive"))
      (node (ref "SIGNAL-IN") (pin "2") (pinfunction "2_2") (pintype "passive"))
      (node (ref "TR010") (pin "1") (pinfunction "TOP_1") (pintype "passive"))
      (node (ref "TR010") (pin "2") (pinfunction "TAP_2") (pintype "passive"))
      (node (ref "TR011") (pin "1") (pinfunction "TOP_1") (pintype "passive"))
      (node (ref "TR011") (pin "2") (pinfunction "TAP_2") (pintype "passive"))
      (node (ref "TR012") (pin "1") (pinfunction "TOP_1") (pintype "passive"))
      (node (ref "TR012") (pin "2") (pinfunction "TAP_2") (pintype "passive"))
      (node (ref "TR013") (pin "1") (pinfunction "TOP_1") (pintype "passive"))
      (node (ref "TR013") (pin "2") (pinfunction "TAP_2") (pintype "passive"))
      (node (ref "TR08") (pin "1") (pinfunction "TOP_1") (pintype "passive"))
      (node (ref "TR08") (pin "2") (pinfunction "TAP_2") (pintype "passive"))
      (node (ref "TR09") (pin "1") (pinfunction "TOP_1") (pintype "passive"))
      (node (ref "TR09") (pin "2") (pinfunction "TAP_2") (pintype "passive"))
      (node (ref "U01") (pin "3") (pinfunction "IN+_3") (pintype "input"))
      (node (ref "U011") (pin "3") (pinfunction "IN+_3") (pintype "input"))
      (node (ref "U012") (pin "3") (pinfunction "IN+_3") (pintype "input"))
      (node (ref "U014") (pin "3") (pinfunction "IN+_3") (pintype "input"))
      (node (ref "U015") (pin "3") (pinfunction "IN+_3") (pintype "input"))
      (node (ref "U08") (pin "3") (pinfunction "IN+_3") (pintype "input"))
      (node (ref "U09") (pin "3") (pinfunction "IN+_3") (pintype "input"))
    )
    (net (code "9") (name "AV+12") (class "Default")
      (node (ref "C026") (pin "1") (pinfunction "1_1") (pintype "passive"))
      (node (ref "C027") (pin "1") (pinfunction "1_1") (pintype "passive"))
      (node (ref "C028") (pin "1") (pinfunction "1_1") (pintype "passive"))
      (node (ref "C029") (pin "1") (pinfunction "1_1") (pintype "passive"))
      (node (ref "C030") (pin "1") (pinfunction "1_1") (pintype "passive"))
      (node (ref "C031") (pin "1") (pinfunction "1_1") (pintype "passive"))
      (node (ref "C038") (pin "1") (pinfunction "1_1") (pintype "passive"))
      (node (ref "C039") (pin "1") (pinfunction "1_1") (pintype "passive"))
      (node (ref "C040") (pin "1") (pinfunction "1_1") (pintype "passive"))
      (node (ref "C041") (pin "1") (pinfunction "1_1") (pintype "passive"))
      (node (ref "C047") (pin "1") (pinfunction "1_1") (pintype "passive"))
      (node (ref "C049") (pin "1") (pinfunction "1_1") (pintype "passive"))
      (node (ref "C051") (pin "1") (pinfunction "1_1") (pintype "passive"))
      (node (ref "C053") (pin "1") (pinfunction "1_1") (pintype "passive"))
      (node (ref "C055") (pin "1") (pinfunction "1_1") (pintype "passive"))
      (node (ref "C065") (pin "1") (pinfunction "1_1") (pintype "passive"))
      (node (ref "C066") (pin "1") (pinfunction "1_1") (pintype "passive"))
      (node (ref "C126") (pin "1") (pinfunction "1_1") (pintype "passive"))
      (node (ref "C127") (pin "1") (pinfunction "1_1") (pintype "passive"))
      (node (ref "C128") (pin "1") (pinfunction "1_1") (pintype "passive"))
      (node (ref "C129") (pin "1") (pinfunction "1_1") (pintype "passive"))
      (node (ref "C130") (pin "1") (pinfunction "1_1") (pintype "passive"))
      (node (ref "C131") (pin "1") (pinfunction "1_1") (pintype "passive"))
      (node (ref "C147") (pin "1") (pinfunction "1_1") (pintype "passive"))
      (node (ref "C149") (pin "1") (pinfunction "1_1") (pintype "passive"))
      (node (ref "C151") (pin "1") (pinfunction "1_1") (pintype "passive"))
      (node (ref "C153") (pin "1") (pinfunction "1_1") (pintype "passive"))
      (node (ref "C155") (pin "1") (pinfunction "1_1") (pintype "passive"))
      (node (ref "U01") (pin "7") (pinfunction "V+_7") (pintype "power_in"))
      (node (ref "U011") (pin "7") (pinfunction "V+_7") (pintype "power_in"))
      (node (ref "U012") (pin "7") (pinfunction "V+_7") (pintype "power_in"))
      (node (ref "U014") (pin "7") (pinfunction "V+_7") (pintype "power_in"))
      (node (ref "U015") (pin "7") (pinfunction "V+_7") (pintype "power_in"))
      (node (ref "U02") (pin "7") (pinfunction "V+_7") (pintype "power_in"))
      (node (ref "U03") (pin "7") (pinfunction "V+_7") (pintype "power_in"))
      (node (ref "U04") (pin "7") (pinfunction "V+_7") (pintype "power_in"))
      (node (ref "U05") (pin "7") (pinfunction "V+_7") (pintype "power_in"))
      (node (ref "U06") (pin "7") (pinfunction "V+_7") (pintype "power_in"))
      (node (ref "U07") (pin "7") (pinfunction "V+_7") (pintype "power_in"))
      (node (ref "U08") (pin "7") (pinfunction "V+_7") (pintype "power_in"))
      (node (ref "U09") (pin "7") (pinfunction "V+_7") (pintype "power_in"))
      (node (ref "UB09") (pin "7") (pinfunction "V+_7") (pintype "power_in"))
      (node (ref "UB12") (pin "7") (pinfunction "V+_7") (pintype "power_in"))
      (node (ref "UB15") (pin "7") (pinfunction "V+_7") (pintype "power_in"))
      (node (ref "±12V") (pin "1") (pinfunction "1_1") (pintype "passive"))
    )
    (net (code "10") (name "AV-12") (class "Default")
      (node (ref "C-32") (pin "1") (pinfunction "1_1") (pintype "passive"))
      (node (ref "C-33") (pin "1") (pinfunction "1_1") (pintype "passive"))
      (node (ref "C-34") (pin "1") (pinfunction "1_1") (pintype "passive"))
      (node (ref "C-35") (pin "1") (pinfunction "1_1") (pintype "passive"))
      (node (ref "C-36") (pin "1") (pinfunction "1_1") (pintype "passive"))
      (node (ref "C-37") (pin "1") (pinfunction "1_1") (pintype "passive"))
      (node (ref "C-48") (pin "1") (pinfunction "1_1") (pintype "passive"))
      (node (ref "C-50") (pin "1") (pinfunction "1_1") (pintype "passive"))
      (node (ref "C-52") (pin "1") (pinfunction "1_1") (pintype "passive"))
      (node (ref "C-54") (pin "1") (pinfunction "1_1") (pintype "passive"))
      (node (ref "C-56") (pin "1") (pinfunction "1_1") (pintype "passive"))
      (node (ref "C032") (pin "1") (pinfunction "1_1") (pintype "passive"))
      (node (ref "C033") (pin "1") (pinfunction "1_1") (pintype "passive"))
      (node (ref "C034") (pin "1") (pinfunction "1_1") (pintype "passive"))
      (node (ref "C035") (pin "1") (pinfunction "1_1") (pintype "passive"))
      (node (ref "C036") (pin "1") (pinfunction "1_1") (pintype "passive"))
      (node (ref "C037") (pin "1") (pinfunction "1_1") (pintype "passive"))
      (node (ref "C042") (pin "2") (pinfunction "2_2") (pintype "passive"))
      (node (ref "C044") (pin "1") (pinfunction "1_1") (pintype "passive"))
      (node (ref "C045") (pin "1") (pinfunction "1_1") (pintype "passive"))
      (node (ref "C046") (pin "1") (pinfunction "1_1") (pintype "passive"))
      (node (ref "C048") (pin "1") (pinfunction "1_1") (pintype "passive"))
      (node (ref "C050") (pin "1") (pinfunction "1_1") (pintype "passive"))
      (node (ref "C052") (pin "1") (pinfunction "1_1") (pintype "passive"))
      (node (ref "C054") (pin "1") (pinfunction "1_1") (pintype "passive"))
      (node (ref "C056") (pin "1") (pinfunction "1_1") (pintype "passive"))
      (node (ref "C059") (pin "1") (pinfunction "1_1") (pintype "passive"))
      (node (ref "C060") (pin "1") (pinfunction "1_1") (pintype "passive"))
      (node (ref "C061") (pin "1") (pinfunction "1_1") (pintype "passive"))
      (node (ref "C062") (pin "1") (pinfunction "1_1") (pintype "passive"))
      (node (ref "U01") (pin "4") (pinfunction "V-_4") (pintype "power_in"))
      (node (ref "U011") (pin "4") (pinfunction "V-_4") (pintype "power_in"))
      (node (ref "U012") (pin "4") (pinfunction "V-_4") (pintype "power_in"))
      (node (ref "U014") (pin "4") (pinfunction "V-_4") (pintype "power_in"))
      (node (ref "U015") (pin "4") (pinfunction "V-_4") (pintype "power_in"))
      (node (ref "U02") (pin "4") (pinfunction "V-_4") (pintype "power_in"))
      (node (ref "U03") (pin "4") (pinfunction "V-_4") (pintype "power_in"))
      (node (ref "U04") (pin "4") (pinfunction "V-_4") (pintype "power_in"))
      (node (ref "U05") (pin "4") (pinfunction "V-_4") (pintype "power_in"))
      (node (ref "U06") (pin "4") (pinfunction "V-_4") (pintype "power_in"))
      (node (ref "U07") (pin "4") (pinfunction "V-_4") (pintype "power_in"))
      (node (ref "U08") (pin "4") (pinfunction "V-_4") (pintype "power_in"))
      (node (ref "U09") (pin "4") (pinfunction "V-_4") (pintype "power_in"))
      (node (ref "UB09") (pin "4") (pinfunction "V-_4") (pintype "power_in"))
      (node (ref "UB12") (pin "4") (pinfunction "V-_4") (pintype "power_in"))
      (node (ref "UB15") (pin "4") (pinfunction "V-_4") (pintype "power_in"))
      (node (ref "±12V") (pin "2") (pinfunction "2_2") (pintype "passive"))
    )
    (net (code "11") (name "GROUPGND") (class "Default")
      (node (ref "C-32") (pin "2") (pinfunction "2_2") (pintype "passive"))
      (node (ref "C-33") (pin "2") (pinfunction "2_2") (pintype "passive"))
      (node (ref "C-34") (pin "2") (pinfunction "2_2") (pintype "passive"))
      (node (ref "C-35") (pin "2") (pinfunction "2_2") (pintype "passive"))
      (node (ref "C-36") (pin "2") (pinfunction "2_2") (pintype "passive"))
      (node (ref "C-37") (pin "2") (pinfunction "2_2") (pintype "passive"))
      (node (ref "C-48") (pin "2") (pinfunction "2_2") (pintype "passive"))
      (node (ref "C-50") (pin "2") (pinfunction "2_2") (pintype "passive"))
      (node (ref "C-52") (pin "2") (pinfunction "2_2") (pintype "passive"))
      (node (ref "C-54") (pin "2") (pinfunction "2_2") (pintype "passive"))
      (node (ref "C-56") (pin "2") (pinfunction "2_2") (pintype "passive"))
      (node (ref "C026") (pin "2") (pinfunction "2_2") (pintype "passive"))
      (node (ref "C027") (pin "2") (pinfunction "2_2") (pintype "passive"))
      (node (ref "C028") (pin "2") (pinfunction "2_2") (pintype "passive"))
      (node (ref "C029") (pin "2") (pinfunction "2_2") (pintype "passive"))
      (node (ref "C030") (pin "2") (pinfunction "2_2") (pintype "passive"))
      (node (ref "C031") (pin "2") (pinfunction "2_2") (pintype "passive"))
      (node (ref "C032") (pin "2") (pinfunction "2_2") (pintype "passive"))
      (node (ref "C033") (pin "2") (pinfunction "2_2") (pintype "passive"))
      (node (ref "C034") (pin "2") (pinfunction "2_2") (pintype "passive"))
      (node (ref "C035") (pin "2") (pinfunction "2_2") (pintype "passive"))
      (node (ref "C036") (pin "2") (pinfunction "2_2") (pintype "passive"))
      (node (ref "C037") (pin "2") (pinfunction "2_2") (pintype "passive"))
      (node (ref "C038") (pin "2") (pinfunction "2_2") (pintype "passive"))
      (node (ref "C039") (pin "2") (pinfunction "2_2") (pintype "passive"))
      (node (ref "C040") (pin "2") (pinfunction "2_2") (pintype "passive"))
      (node (ref "C041") (pin "2") (pinfunction "2_2") (pintype "passive"))
      (node (ref "C042") (pin "1") (pinfunction "1_1") (pintype "passive"))
      (node (ref "C044") (pin "2") (pinfunction "2_2") (pintype "passive"))
      (node (ref "C045") (pin "2") (pinfunction "2_2") (pintype "passive"))
      (node (ref "C046") (pin "2") (pinfunction "2_2") (pintype "passive"))
      (node (ref "C047") (pin "2") (pinfunction "2_2") (pintype "passive"))
      (node (ref "C048") (pin "2") (pinfunction "2_2") (pintype "passive"))
      (node (ref "C049") (pin "2") (pinfunction "2_2") (pintype "passive"))
      (node (ref "C050") (pin "2") (pinfunction "2_2") (pintype "passive"))
      (node (ref "C051") (pin "2") (pinfunction "2_2") (pintype "passive"))
      (node (ref "C052") (pin "2") (pinfunction "2_2") (pintype "passive"))
      (node (ref "C053") (pin "2") (pinfunction "2_2") (pintype "passive"))
      (node (ref "C054") (pin "2") (pinfunction "2_2") (pintype "passive"))
      (node (ref "C055") (pin "2") (pinfunction "2_2") (pintype "passive"))
      (node (ref "C056") (pin "2") (pinfunction "2_2") (pintype "passive"))
      (node (ref "C059") (pin "2") (pinfunction "2_2") (pintype "passive"))
      (node (ref "C060") (pin "2") (pinfunction "2_2") (pintype "passive"))
      (node (ref "C061") (pin "2") (pinfunction "2_2") (pintype "passive"))
      (node (ref "C062") (pin "2") (pinfunction "2_2") (pintype "passive"))
      (node (ref "C065") (pin "2") (pinfunction "2_2") (pintype "passive"))
      (node (ref "C066") (pin "2") (pinfunction "2_2") (pintype "passive"))
      (node (ref "C126") (pin "2") (pinfunction "2_2") (pintype "passive"))
      (node (ref "C127") (pin "2") (pinfunction "2_2") (pintype "passive"))
      (node (ref "C128") (pin "2") (pinfunction "2_2") (pintype "passive"))
      (node (ref "C129") (pin "2") (pinfunction "2_2") (pintype "passive"))
      (node (ref "C130") (pin "2") (pinfunction "2_2") (pintype "passive"))
      (node (ref "C131") (pin "2") (pinfunction "2_2") (pintype "passive"))
      (node (ref "C147") (pin "2") (pinfunction "2_2") (pintype "passive"))
      (node (ref "C149") (pin "2") (pinfunction "2_2") (pintype "passive"))
      (node (ref "C151") (pin "2") (pinfunction "2_2") (pintype "passive"))
      (node (ref "C153") (pin "2") (pinfunction "2_2") (pintype "passive"))
      (node (ref "C155") (pin "2") (pinfunction "2_2") (pintype "passive"))
      (node (ref "RGND") (pin "2") (pinfunction "2_2") (pintype "passive"))
      (node (ref "±12V") (pin "3") (pinfunction "3_3") (pintype "passive"))
    )
    (net (code "12") (name "Net-(C002-Pad1)") (class "Default")
      (node (ref "C002") (pin "1") (pinfunction "1_1") (pintype "passive"))
      (node (ref "R02") (pin "2") (pinfunction "2_2") (pintype "passive"))
      (node (ref "R03") (pin "1") (pinfunction "1_1") (pintype "passive"))
    )
    (net (code "13") (name "Net-(C004-Pad1)") (class "Default")
      (node (ref "C004") (pin "1") (pinfunction "1_1") (pintype "passive"))
      (node (ref "R07") (pin "2") (pinfunction "2_2") (pintype "passive"))
      (node (ref "R08") (pin "1") (pinfunction "1_1") (pintype "passive"))
    )
    (net (code "14") (name "Net-(C006-Pad1)") (class "Default")
      (node (ref "C006") (pin "1") (pinfunction "1_1") (pintype "passive"))
      (node (ref "C007") (pin "2") (pinfunction "2_2") (pintype "passive"))
      (node (ref "R013") (pin "2") (pinfunction "2_2") (pintype "passive"))
    )
    (net (code "15") (name "Net-(C009-Pad2)") (class "Default")
      (node (ref "C009") (pin "2") (pinfunction "2_2") (pintype "passive"))
      (node (ref "R014") (pin "2") (pinfunction "2_2") (pintype "passive"))
      (node (ref "R015") (pin "2") (pinfunction "2_2") (pintype "passive"))
    )
    (net (code "16") (name "Net-(C013-Pad2)") (class "Default")
      (node (ref "C013") (pin "2") (pinfunction "2_2") (pintype "passive"))
      (node (ref "R018") (pin "2") (pinfunction "2_2") (pintype "passive"))
      (node (ref "R019") (pin "1") (pinfunction "1_1") (pintype "passive"))
    )
    (net (code "17") (name "Net-(C014-Pad2)") (class "Default")
      (node (ref "C014") (pin "2") (pinfunction "2_2") (pintype "passive"))
      (node (ref "C015") (pin "2") (pinfunction "2_2") (pintype "passive"))
      (node (ref "R020") (pin "2") (pinfunction "2_2") (pintype "passive"))
      (node (ref "R021") (pin "2") (pinfunction "2_2") (pintype "passive"))
    )
    (net (code "18") (name "Net-(C016-Pad2)") (class "Default")
      (node (ref "C016") (pin "2") (pinfunction "2_2") (pintype "passive"))
      (node (ref "C017") (pin "2") (pinfunction "2_2") (pintype "passive"))
      (node (ref "R024") (pin "2") (pinfunction "2_2") (pintype "passive"))
      (node (ref "R025") (pin "2") (pinfunction "2_2") (pintype "passive"))
    )
    (net (code "19") (name "Net-(C018-Pad2)") (class "Default")
      (node (ref "C018") (pin "2") (pinfunction "2_2") (pintype "passive"))
      (node (ref "C019") (pin "2") (pinfunction "2_2") (pintype "passive"))
      (node (ref "R033") (pin "2") (pinfunction "2_2") (pintype "passive"))
      (node (ref "R034") (pin "2") (pinfunction "2_2") (pintype "passive"))
    )
    (net (code "20") (name "Net-(C020-Pad2)") (class "Default")
      (node (ref "C020") (pin "2") (pinfunction "2_2") (pintype "passive"))
      (node (ref "C021") (pin "2") (pinfunction "2_2") (pintype "passive"))
      (node (ref "R037") (pin "2") (pinfunction "2_2") (pintype "passive"))
      (node (ref "R038") (pin "2") (pinfunction "2_2") (pintype "passive"))
    )
    (net (code "21") (name "Net-(C022-Pad2)") (class "Default")
      (node (ref "C022") (pin "2") (pinfunction "2_2") (pintype "passive"))
      (node (ref "C023") (pin "2") (pinfunction "2_2") (pintype "passive"))
      (node (ref "R046") (pin "2") (pinfunction "2_2") (pintype "passive"))
      (node (ref "R047") (pin "2") (pinfunction "2_2") (pintype "passive"))
    )
    (net (code "22") (name "Net-(C024-Pad2)") (class "Default")
      (node (ref "C024") (pin "2") (pinfunction "2_2") (pintype "passive"))
      (node (ref "C025") (pin "2") (pinfunction "2_2") (pintype "passive"))
      (node (ref "R050") (pin "2") (pinfunction "2_2") (pintype "passive"))
      (node (ref "R051") (pin "2") (pinfunction "2_2") (pintype "passive"))
    )
    (net (code "23") (name "Net-(CO11-Pad2)") (class "Default")
      (node (ref "CO11") (pin "2") (pinfunction "2_2") (pintype "passive"))
      (node (ref "R016") (pin "2") (pinfunction "2_2") (pintype "passive"))
      (node (ref "R017") (pin "1") (pinfunction "1_1") (pintype "passive"))
    )
    (net (code "24") (name "Net-(R05-Pad2)") (class "Default")
      (node (ref "R05") (pin "2") (pinfunction "2_2") (pintype "passive"))
      (node (ref "R06") (pin "1") (pinfunction "1_1") (pintype "passive"))
    )
    (net (code "25") (name "Net-(R010-Pad2)") (class "Default")
      (node (ref "R010") (pin "2") (pinfunction "2_2") (pintype "passive"))
      (node (ref "R011") (pin "1") (pinfunction "1_1") (pintype "passive"))
    )
    (net (code "26") (name "Net-(TR08-BOT)") (class "Default")
      (node (ref "R021") (pin "1") (pinfunction "1_1") (pintype "passive"))
      (node (ref "TR08") (pin "3") (pinfunction "BOT_3") (pintype "passive"))
    )
    (net (code "27") (name "Net-(TR09-BOT)") (class "Default")
      (node (ref "R025") (pin "1") (pinfunction "1_1") (pintype "passive"))
      (node (ref "TR09") (pin "3") (pinfunction "BOT_3") (pintype "passive"))
    )
    (net (code "28") (name "Net-(TR010-BOT)") (class "Default")
      (node (ref "R034") (pin "1") (pinfunction "1_1") (pintype "passive"))
      (node (ref "TR010") (pin "3") (pinfunction "BOT_3") (pintype "passive"))
    )
    (net (code "29") (name "Net-(TR011-BOT)") (class "Default")
      (node (ref "R038") (pin "1") (pinfunction "1_1") (pintype "passive"))
      (node (ref "TR011") (pin "3") (pinfunction "BOT_3") (pintype "passive"))
    )
    (net (code "30") (name "Net-(TR012-BOT)") (class "Default")
      (node (ref "R047") (pin "1") (pinfunction "1_1") (pintype "passive"))
      (node (ref "TR012") (pin "3") (pinfunction "BOT_3") (pintype "passive"))
    )
    (net (code "31") (name "Net-(TR013-BOT)") (class "Default")
      (node (ref "R051") (pin "1") (pinfunction "1_1") (pintype "passive"))
      (node (ref "TR013") (pin "3") (pinfunction "BOT_3") (pintype "passive"))
    )
    (net (code "32") (name "Net-(U01-IN-)") (class "Default")
      (node (ref "C001") (pin "2") (pinfunction "2_2") (pintype "passive"))
      (node (ref "R01") (pin "1") (pinfunction "1_1") (pintype "passive"))
      (node (ref "SIGNAL-IN") (pin "3") (pinfunction "3_3") (pintype "passive"))
      (node (ref "U01") (pin "2") (pinfunction "IN-_2") (pintype "input"))
    )
    (net (code "33") (name "Net-(U01-OUT)") (class "Default")
      (node (ref "C001") (pin "1") (pinfunction "1_1") (pintype "passive"))
      (node (ref "C002") (pin "2") (pinfunction "2_2") (pintype "passive"))
      (node (ref "R01") (pin "2") (pinfunction "2_2") (pintype "passive"))
      (node (ref "U01") (pin "6") (pinfunction "OUT_6") (pintype "output"))
    )
    (net (code "34") (name "Net-(U02-IN+)") (class "Default")
      (node (ref "R03") (pin "2") (pinfunction "2_2") (pintype "passive"))
      (node (ref "U02") (pin "3") (pinfunction "IN+_3") (pintype "input"))
    )
    (net (code "35") (name "Net-(U02-IN-)") (class "Default")
      (node (ref "C003") (pin "2") (pinfunction "2_2") (pintype "passive"))
      (node (ref "R04") (pin "2") (pinfunction "2_2") (pintype "passive"))
      (node (ref "R05") (pin "1") (pinfunction "1_1") (pintype "passive"))
      (node (ref "U02") (pin "2") (pinfunction "IN-_2") (pintype "input"))
    )
    (net (code "36") (name "Net-(U02-OUT)") (class "Default")
      (node (ref "C003") (pin "1") (pinfunction "1_1") (pintype "passive"))
      (node (ref "C004") (pin "2") (pinfunction "2_2") (pintype "passive"))
      (node (ref "R06") (pin "2") (pinfunction "2_2") (pintype "passive"))
      (node (ref "U02") (pin "6") (pinfunction "OUT_6") (pintype "output"))
    )
    (net (code "37") (name "Net-(U03-IN+)") (class "Default")
      (node (ref "R08") (pin "2") (pinfunction "2_2") (pintype "passive"))
      (node (ref "U03") (pin "3") (pinfunction "IN+_3") (pintype "input"))
    )
    (net (code "38") (name "Net-(U03-IN-)") (class "Default")
      (node (ref "C005") (pin "2") (pinfunction "2_2") (pintype "passive"))
      (node (ref "R010") (pin "1") (pinfunction "1_1") (pintype "passive"))
      (node (ref "R09") (pin "2") (pinfunction "2_2") (pintype "passive"))
      (node (ref "U03") (pin "2") (pinfunction "IN-_2") (pintype "input"))
    )
    (net (code "39") (name "Net-(U04-IN+)") (class "Default")
      (node (ref "C007") (pin "1") (pinfunction "1_1") (pintype "passive"))
      (node (ref "R012") (pin "2") (pinfunction "2_2") (pintype "passive"))
      (node (ref "U04") (pin "3") (pinfunction "IN+_3") (pintype "input"))
    )
    (net (code "40") (name "Net-(U04-IN-)") (class "Default")
      (node (ref "R013") (pin "1") (pinfunction "1_1") (pintype "passive"))
      (node (ref "R014") (pin "1") (pinfunction "1_1") (pintype "passive"))
      (node (ref "U04") (pin "2") (pinfunction "IN-_2") (pintype "input"))
      (node (ref "U04") (pin "6") (pinfunction "OUT_6") (pintype "output"))
    )
    (net (code "41") (name "Net-(U05-IN+)") (class "Default")
      (node (ref "C008") (pin "1") (pinfunction "1_1") (pintype "passive"))
      (node (ref "R015") (pin "1") (pinfunction "1_1") (pintype "passive"))
      (node (ref "U05") (pin "3") (pinfunction "IN+_3") (pintype "input"))
    )
    (net (code "42") (name "Net-(U05-IN-)") (class "Default")
      (node (ref "C009") (pin "1") (pinfunction "1_1") (pintype "passive"))
      (node (ref "R016") (pin "1") (pinfunction "1_1") (pintype "passive"))
      (node (ref "U05") (pin "2") (pinfunction "IN-_2") (pintype "input"))
      (node (ref "U05") (pin "6") (pinfunction "OUT_6") (pintype "output"))
    )
    (net (code "43") (name "Net-(U06-IN+)") (class "Default")
      (node (ref "CO10") (pin "2") (pinfunction "2_2") (pintype "passive"))
      (node (ref "R017") (pin "2") (pinfunction "2_2") (pintype "passive"))
      (node (ref "U06") (pin "3") (pinfunction "IN+_3") (pintype "input"))
    )
    (net (code "44") (name "Net-(U06-IN-)") (class "Default")
      (node (ref "CO11") (pin "1") (pinfunction "1_1") (pintype "passive"))
      (node (ref "R018") (pin "1") (pinfunction "1_1") (pintype "passive"))
      (node (ref "U06") (pin "2") (pinfunction "IN-_2") (pintype "input"))
      (node (ref "U06") (pin "6") (pinfunction "OUT_6") (pintype "output"))
    )
    (net (code "45") (name "Net-(U07-IN+)") (class "Default")
      (node (ref "CO12") (pin "2") (pinfunction "2_2") (pintype "passive"))
      (node (ref "R019") (pin "2") (pinfunction "2_2") (pintype "passive"))
      (node (ref "U07") (pin "3") (pinfunction "IN+_3") (pintype "input"))
    )
    (net (code "46") (name "Net-(U08-IN-)") (class "Default")
      (node (ref "C015") (pin "1") (pinfunction "1_1") (pintype "passive"))
      (node (ref "R022") (pin "1") (pinfunction "1_1") (pintype "passive"))
      (node (ref "U08") (pin "2") (pinfunction "IN-_2") (pintype "input"))
    )
    (net (code "47") (name "Net-(U08-OUT)") (class "Default")
      (node (ref "C014") (pin "1") (pinfunction "1_1") (pintype "passive"))
      (node (ref "R022") (pin "2") (pinfunction "2_2") (pintype "passive"))
      (node (ref "R024") (pin "1") (pinfunction "1_1") (pintype "passive"))
      (node (ref "U08") (pin "6") (pinfunction "OUT_6") (pintype "output"))
    )
    (net (code "48") (name "Net-(U09-IN-)") (class "Default")
      (node (ref "C017") (pin "1") (pinfunction "1_1") (pintype "passive"))
      (node (ref "R026") (pin "1") (pinfunction "1_1") (pintype "passive"))
      (node (ref "U09") (pin "2") (pinfunction "IN-_2") (pintype "input"))
    )
    (net (code "49") (name "Net-(U09-OUT)") (class "Default")
      (node (ref "C016") (pin "1") (pinfunction "1_1") (pintype "passive"))
      (node (ref "R026") (pin "2") (pinfunction "2_2") (pintype "passive"))
      (node (ref "R027") (pin "2") (pinfunction "2_2") (pintype "passive"))
      (node (ref "RL17") (pin "2") (pinfunction "2_2") (pintype "passive"))
      (node (ref "U09") (pin "6") (pinfunction "OUT_6") (pintype "output"))
    )
    (net (code "50") (name "Net-(U011-IN-)") (class "Default")
      (node (ref "C019") (pin "1") (pinfunction "1_1") (pintype "passive"))
      (node (ref "R035") (pin "1") (pinfunction "1_1") (pintype "passive"))
      (node (ref "U011") (pin "2") (pinfunction "IN-_2") (pintype "input"))
    )
    (net (code "51") (name "Net-(U011-OUT)") (class "Default")
      (node (ref "C018") (pin "1") (pinfunction "1_1") (pintype "passive"))
      (node (ref "R035") (pin "2") (pinfunction "2_2") (pintype "passive"))
      (node (ref "R037") (pin "1") (pinfunction "1_1") (pintype "passive"))
      (node (ref "U011") (pin "6") (pinfunction "OUT_6") (pintype "output"))
    )
    (net (code "52") (name "Net-(U012-IN-)") (class "Default")
      (node (ref "C021") (pin "1") (pinfunction "1_1") (pintype "passive"))
      (node (ref "R039") (pin "1") (pinfunction "1_1") (pintype "passive"))
      (node (ref "U012") (pin "2") (pinfunction "IN-_2") (pintype "input"))
    )
    (net (code "53") (name "Net-(U012-OUT)") (class "Default")
      (node (ref "C020") (pin "1") (pinfunction "1_1") (pintype "passive"))
      (node (ref "R039") (pin "2") (pinfunction "2_2") (pintype "passive"))
      (node (ref "R040") (pin "2") (pinfunction "2_2") (pintype "passive"))
      (node (ref "RL19") (pin "2") (pinfunction "2_2") (pintype "passive"))
      (node (ref "U012") (pin "6") (pinfunction "OUT_6") (pintype "output"))
    )
    (net (code "54") (name "Net-(U014-IN-)") (class "Default")
      (node (ref "C023") (pin "1") (pinfunction "1_1") (pintype "passive"))
      (node (ref "R048") (pin "1") (pinfunction "1_1") (pintype "passive"))
      (node (ref "U014") (pin "2") (pinfunction "IN-_2") (pintype "input"))
    )
    (net (code "55") (name "Net-(U014-OUT)") (class "Default")
      (node (ref "C022") (pin "1") (pinfunction "1_1") (pintype "passive"))
      (node (ref "R048") (pin "2") (pinfunction "2_2") (pintype "passive"))
      (node (ref "R050") (pin "1") (pinfunction "1_1") (pintype "passive"))
      (node (ref "U014") (pin "6") (pinfunction "OUT_6") (pintype "output"))
    )
    (net (code "56") (name "Net-(U015-IN-)") (class "Default")
      (node (ref "C025") (pin "1") (pinfunction "1_1") (pintype "passive"))
      (node (ref "R052") (pin "1") (pinfunction "1_1") (pintype "passive"))
      (node (ref "U015") (pin "2") (pinfunction "IN-_2") (pintype "input"))
    )
    (net (code "57") (name "Net-(U015-OUT)") (class "Default")
      (node (ref "C024") (pin "1") (pinfunction "1_1") (pintype "passive"))
      (node (ref "R052") (pin "2") (pinfunction "2_2") (pintype "passive"))
      (node (ref "R053") (pin "2") (pinfunction "2_2") (pintype "passive"))
      (node (ref "RL22") (pin "2") (pinfunction "2_2") (pintype "passive"))
      (node (ref "U015") (pin "6") (pinfunction "OUT_6") (pintype "output"))
    )
    (net (code "58") (name "Net-(UB09-IN+)") (class "Default")
      (node (ref "R027") (pin "1") (pinfunction "1_1") (pintype "passive"))
      (node (ref "UB09") (pin "3") (pinfunction "IN+_3") (pintype "input"))
    )
    (net (code "59") (name "Net-(UB12-IN+)") (class "Default")
      (node (ref "R040") (pin "1") (pinfunction "1_1") (pintype "passive"))
      (node (ref "UB12") (pin "3") (pinfunction "IN+_3") (pintype "input"))
    )
    (net (code "60") (name "Net-(UB15-IN+)") (class "Default")
      (node (ref "R053") (pin "1") (pinfunction "1_1") (pintype "passive"))
      (node (ref "UB15") (pin "3") (pinfunction "IN+_3") (pintype "input"))
    )
    (net (code "61") (name "unconnected-(U01-BAL-Pad1)") (class "Default")
      (node (ref "U01") (pin "1") (pinfunction "BAL_1") (pintype "passive+no_connect"))
    )
    (net (code "62") (name "unconnected-(U01-BAL-Pad8)") (class "Default")
      (node (ref "U01") (pin "8") (pinfunction "BAL_8") (pintype "passive+no_connect"))
    )
    (net (code "63") (name "unconnected-(U01-NC-Pad5)") (class "Default")
      (node (ref "U01") (pin "5") (pinfunction "NC_5") (pintype "passive+no_connect"))
    )
    (net (code "64") (name "unconnected-(U02-NC-Pad5)") (class "Default")
      (node (ref "U02") (pin "5") (pinfunction "NC_5") (pintype "passive+no_connect"))
    )
    (net (code "65") (name "unconnected-(U02-VOSTRIM-Pad1)") (class "Default")
      (node (ref "U02") (pin "1") (pinfunction "VOSTRIM_1") (pintype "passive+no_connect"))
    )
    (net (code "66") (name "unconnected-(U02-VOSTRIM-Pad8)") (class "Default")
      (node (ref "U02") (pin "8") (pinfunction "VOSTRIM_8") (pintype "passive+no_connect"))
    )
    (net (code "67") (name "unconnected-(U03-NC-Pad5)") (class "Default")
      (node (ref "U03") (pin "5") (pinfunction "NC_5") (pintype "passive+no_connect"))
    )
    (net (code "68") (name "unconnected-(U03-VOSTRIM-Pad1)") (class "Default")
      (node (ref "U03") (pin "1") (pinfunction "VOSTRIM_1") (pintype "passive+no_connect"))
    )
    (net (code "69") (name "unconnected-(U03-VOSTRIM-Pad8)") (class "Default")
      (node (ref "U03") (pin "8") (pinfunction "VOSTRIM_8") (pintype "passive+no_connect"))
    )
    (net (code "70") (name "unconnected-(U04-NC-Pad5)") (class "Default")
      (node (ref "U04") (pin "5") (pinfunction "NC_5") (pintype "passive+no_connect"))
    )
    (net (code "71") (name "unconnected-(U04-VOSTRIM-Pad1)") (class "Default")
      (node (ref "U04") (pin "1") (pinfunction "VOSTRIM_1") (pintype "passive+no_connect"))
    )
    (net (code "72") (name "unconnected-(U04-VOSTRIM-Pad8)") (class "Default")
      (node (ref "U04") (pin "8") (pinfunction "VOSTRIM_8") (pintype "passive+no_connect"))
    )
    (net (code "73") (name "unconnected-(U05-NC-Pad5)") (class "Default")
      (node (ref "U05") (pin "5") (pinfunction "NC_5") (pintype "passive+no_connect"))
    )
    (net (code "74") (name "unconnected-(U05-VOSTRIM-Pad1)") (class "Default")
      (node (ref "U05") (pin "1") (pinfunction "VOSTRIM_1") (pintype "passive+no_connect"))
    )
    (net (code "75") (name "unconnected-(U05-VOSTRIM-Pad8)") (class "Default")
      (node (ref "U05") (pin "8") (pinfunction "VOSTRIM_8") (pintype "passive+no_connect"))
    )
    (net (code "76") (name "unconnected-(U06-NC-Pad5)") (class "Default")
      (node (ref "U06") (pin "5") (pinfunction "NC_5") (pintype "passive+no_connect"))
    )
    (net (code "77") (name "unconnected-(U06-VOSTRIM-Pad1)") (class "Default")
      (node (ref "U06") (pin "1") (pinfunction "VOSTRIM_1") (pintype "passive+no_connect"))
    )
    (net (code "78") (name "unconnected-(U06-VOSTRIM-Pad8)") (class "Default")
      (node (ref "U06") (pin "8") (pinfunction "VOSTRIM_8") (pintype "passive+no_connect"))
    )
    (net (code "79") (name "unconnected-(U07-NC-Pad5)") (class "Default")
      (node (ref "U07") (pin "5") (pinfunction "NC_5") (pintype "passive+no_connect"))
    )
    (net (code "80") (name "unconnected-(U07-VOSTRIM-Pad1)") (class "Default")
      (node (ref "U07") (pin "1") (pinfunction "VOSTRIM_1") (pintype "passive+no_connect"))
    )
    (net (code "81") (name "unconnected-(U07-VOSTRIM-Pad8)") (class "Default")
      (node (ref "U07") (pin "8") (pinfunction "VOSTRIM_8") (pintype "passive+no_connect"))
    )
    (net (code "82") (name "unconnected-(U08-NC-Pad5)") (class "Default")
      (node (ref "U08") (pin "5") (pinfunction "NC_5") (pintype "passive+no_connect"))
    )
    (net (code "83") (name "unconnected-(U08-VOSTRIM-Pad1)") (class "Default")
      (node (ref "U08") (pin "1") (pinfunction "VOSTRIM_1") (pintype "passive+no_connect"))
    )
    (net (code "84") (name "unconnected-(U08-VOSTRIM-Pad8)") (class "Default")
      (node (ref "U08") (pin "8") (pinfunction "VOSTRIM_8") (pintype "passive+no_connect"))
    )
    (net (code "85") (name "unconnected-(U09-NC-Pad5)") (class "Default")
      (node (ref "U09") (pin "5") (pinfunction "NC_5") (pintype "passive+no_connect"))
    )
    (net (code "86") (name "unconnected-(U09-VOSTRIM-Pad1)") (class "Default")
      (node (ref "U09") (pin "1") (pinfunction "VOSTRIM_1") (pintype "passive+no_connect"))
    )
    (net (code "87") (name "unconnected-(U09-VOSTRIM-Pad8)") (class "Default")
      (node (ref "U09") (pin "8") (pinfunction "VOSTRIM_8") (pintype "passive+no_connect"))
    )
    (net (code "88") (name "unconnected-(U011-NC-Pad5)") (class "Default")
      (node (ref "U011") (pin "5") (pinfunction "NC_5") (pintype "passive+no_connect"))
    )
    (net (code "89") (name "unconnected-(U011-VOSTRIM-Pad1)") (class "Default")
      (node (ref "U011") (pin "1") (pinfunction "VOSTRIM_1") (pintype "passive+no_connect"))
    )
    (net (code "90") (name "unconnected-(U011-VOSTRIM-Pad8)") (class "Default")
      (node (ref "U011") (pin "8") (pinfunction "VOSTRIM_8") (pintype "passive+no_connect"))
    )
    (net (code "91") (name "unconnected-(U012-NC-Pad5)") (class "Default")
      (node (ref "U012") (pin "5") (pinfunction "NC_5") (pintype "passive+no_connect"))
    )
    (net (code "92") (name "unconnected-(U012-VOSTRIM-Pad1)") (class "Default")
      (node (ref "U012") (pin "1") (pinfunction "VOSTRIM_1") (pintype "passive+no_connect"))
    )
    (net (code "93") (name "unconnected-(U012-VOSTRIM-Pad8)") (class "Default")
      (node (ref "U012") (pin "8") (pinfunction "VOSTRIM_8") (pintype "passive+no_connect"))
    )
    (net (code "94") (name "unconnected-(U014-NC-Pad5)") (class "Default")
      (node (ref "U014") (pin "5") (pinfunction "NC_5") (pintype "passive+no_connect"))
    )
    (net (code "95") (name "unconnected-(U014-VOSTRIM-Pad1)") (class "Default")
      (node (ref "U014") (pin "1") (pinfunction "VOSTRIM_1") (pintype "passive+no_connect"))
    )
    (net (code "96") (name "unconnected-(U014-VOSTRIM-Pad8)") (class "Default")
      (node (ref "U014") (pin "8") (pinfunction "VOSTRIM_8") (pintype "passive+no_connect"))
    )
    (net (code "97") (name "unconnected-(U015-NC-Pad5)") (class "Default")
      (node (ref "U015") (pin "5") (pinfunction "NC_5") (pintype "passive+no_connect"))
    )
    (net (code "98") (name "unconnected-(U015-VOSTRIM-Pad1)") (class "Default")
      (node (ref "U015") (pin "1") (pinfunction "VOSTRIM_1") (pintype "passive+no_connect"))
    )
    (net (code "99") (name "unconnected-(U015-VOSTRIM-Pad8)") (class "Default")
      (node (ref "U015") (pin "8") (pinfunction "VOSTRIM_8") (pintype "passive+no_connect"))
    )
    (net (code "100") (name "unconnected-(UB09-NC-Pad5)") (class "Default")
      (node (ref "UB09") (pin "5") (pinfunction "NC_5") (pintype "passive+no_connect"))
    )
    (net (code "101") (name "unconnected-(UB09-VOSTRIM-Pad1)") (class "Default")
      (node (ref "UB09") (pin "1") (pinfunction "VOSTRIM_1") (pintype "passive+no_connect"))
    )
    (net (code "102") (name "unconnected-(UB09-VOSTRIM-Pad8)") (class "Default")
      (node (ref "UB09") (pin "8") (pinfunction "VOSTRIM_8") (pintype "passive+no_connect"))
    )
    (net (code "103") (name "unconnected-(UB12-NC-Pad5)") (class "Default")
      (node (ref "UB12") (pin "5") (pinfunction "NC_5") (pintype "passive+no_connect"))
    )
    (net (code "104") (name "unconnected-(UB12-VOSTRIM-Pad1)") (class "Default")
      (node (ref "UB12") (pin "1") (pinfunction "VOSTRIM_1") (pintype "passive+no_connect"))
    )
    (net (code "105") (name "unconnected-(UB12-VOSTRIM-Pad8)") (class "Default")
      (node (ref "UB12") (pin "8") (pinfunction "VOSTRIM_8") (pintype "passive+no_connect"))
    )
    (net (code "106") (name "unconnected-(UB15-NC-Pad5)") (class "Default")
      (node (ref "UB15") (pin "5") (pinfunction "NC_5") (pintype "passive+no_connect"))
    )
    (net (code "107") (name "unconnected-(UB15-VOSTRIM-Pad1)") (class "Default")
      (node (ref "UB15") (pin "1") (pinfunction "VOSTRIM_1") (pintype "passive+no_connect"))
    )
    (net (code "108") (name "unconnected-(UB15-VOSTRIM-Pad8)") (class "Default")
      (node (ref "UB15") (pin "8") (pinfunction "VOSTRIM_8") (pintype "passive+no_connect"))
    )
  )
)
